# MainBoard.net
KiCad netlist of a schematic drawn in EAGLE
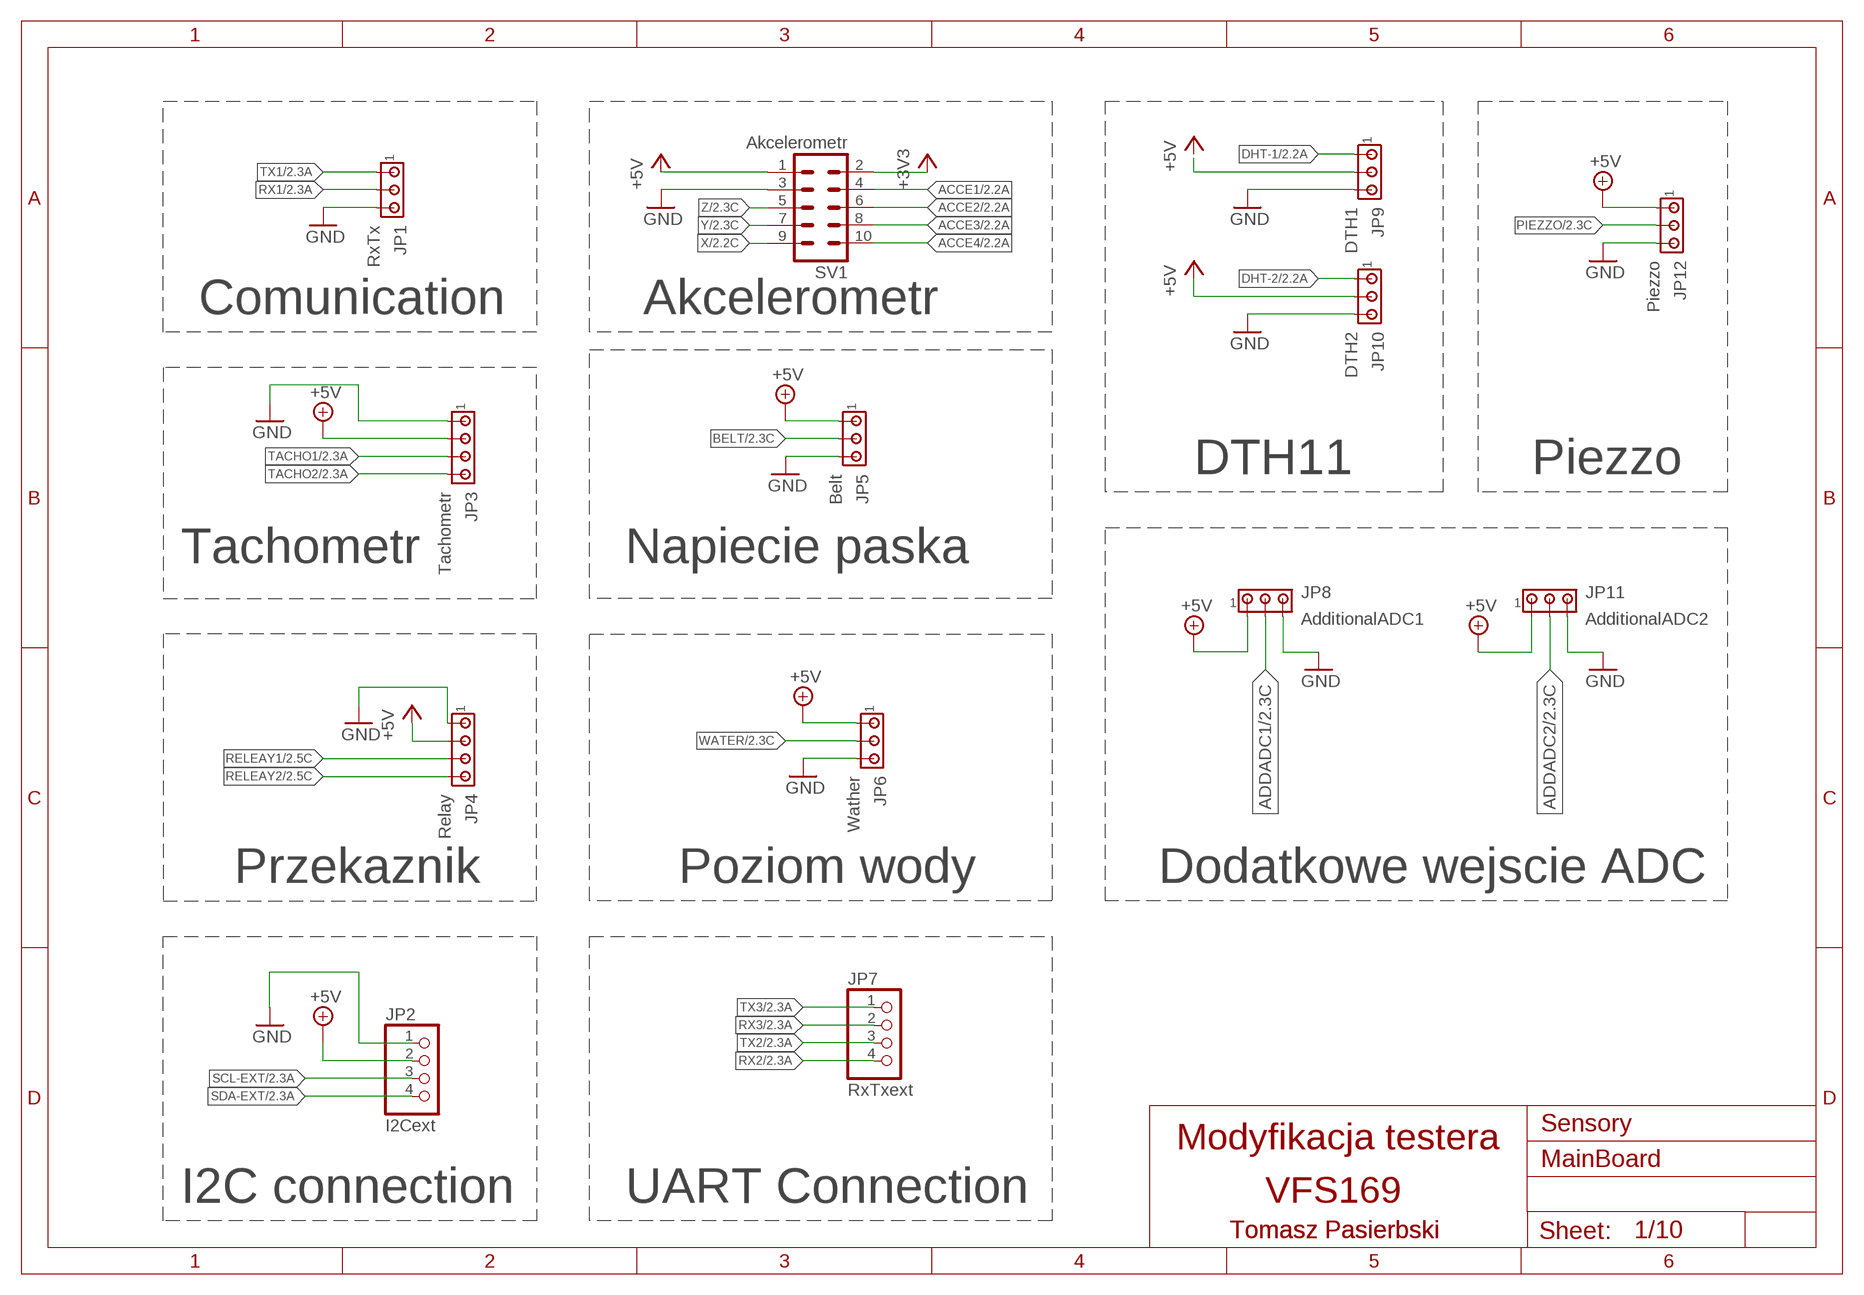
[diagram p0: schematic, sheet 1]
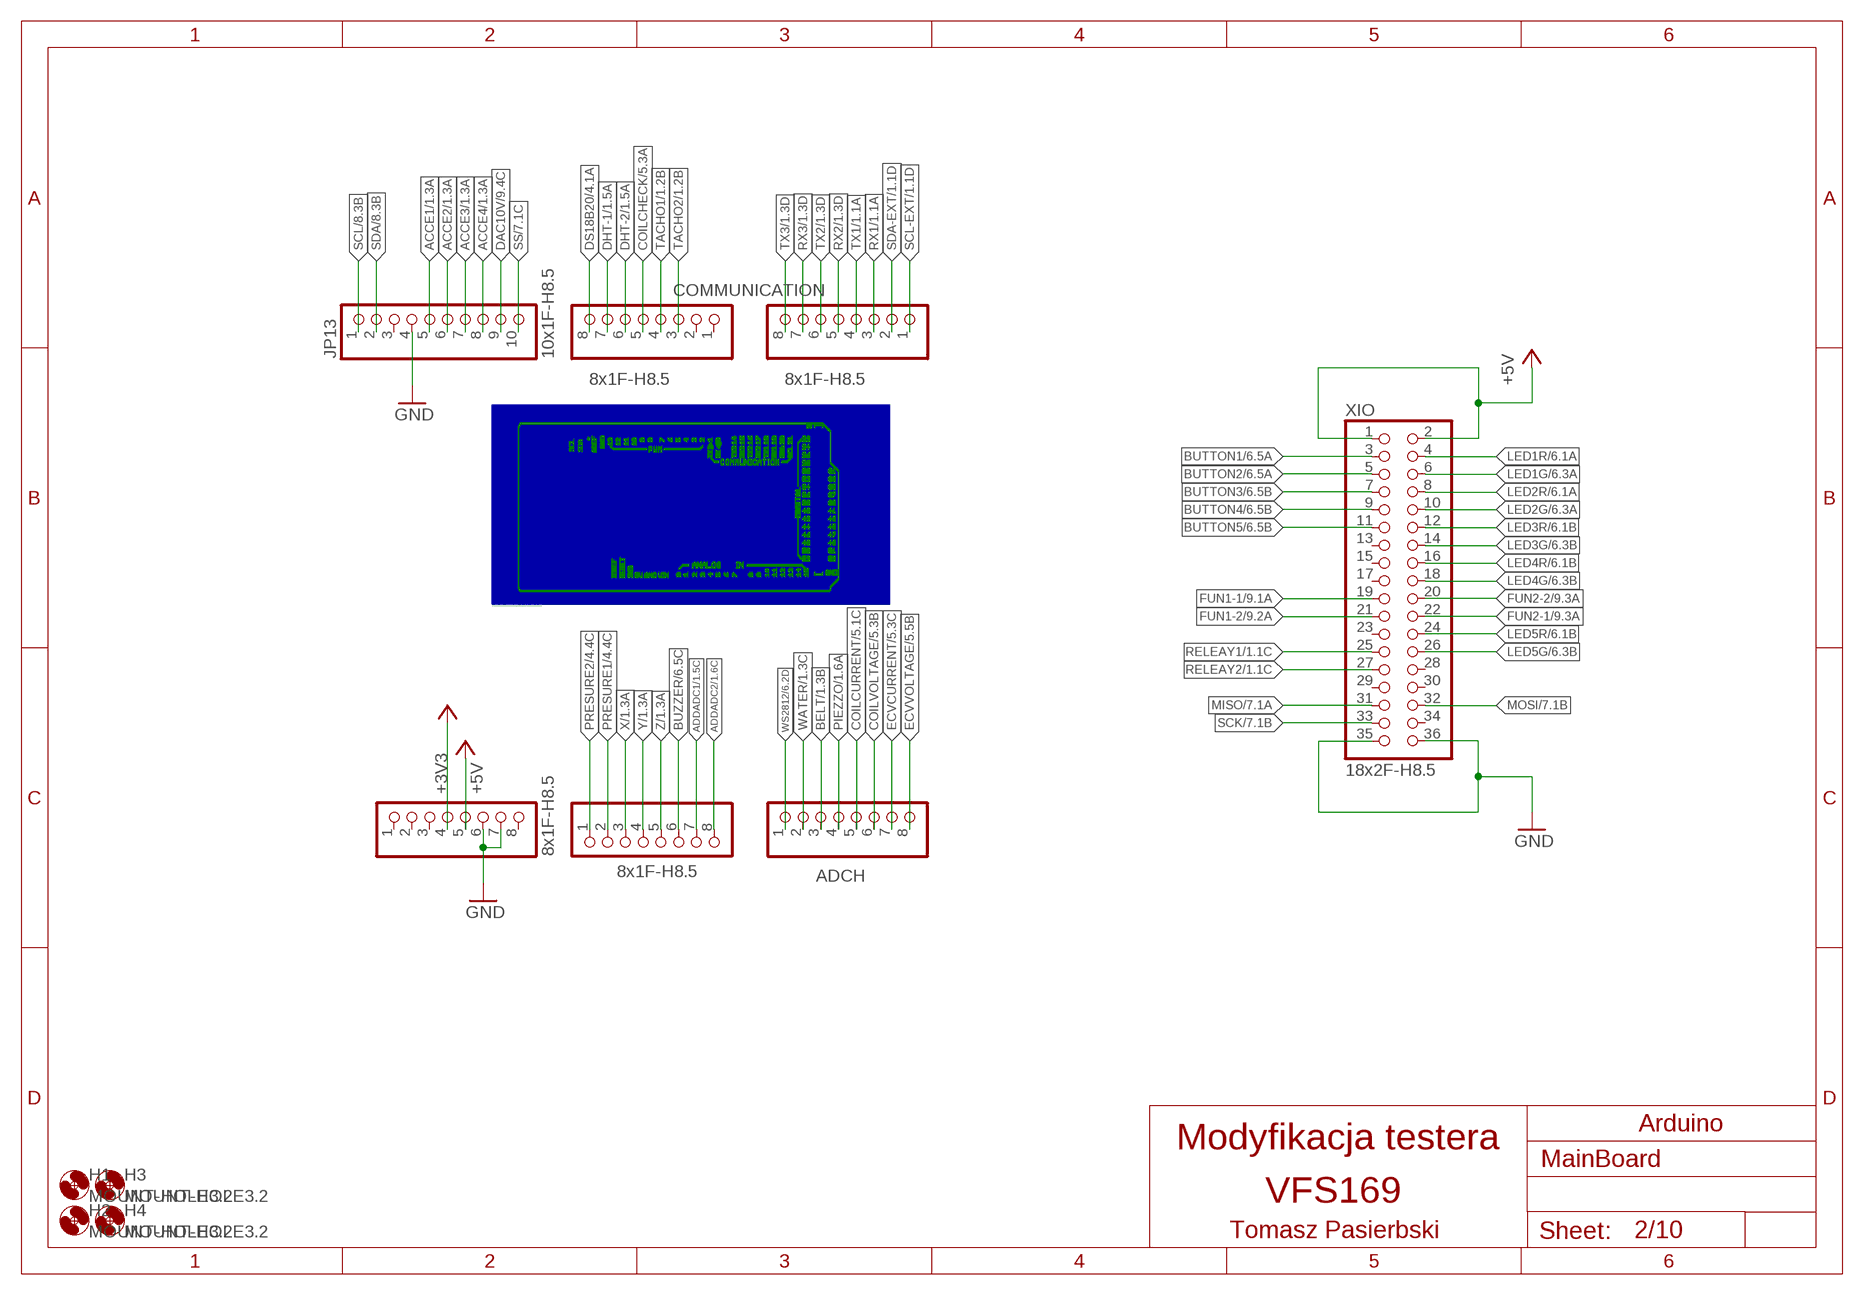
[diagram p1: schematic, sheet 2]
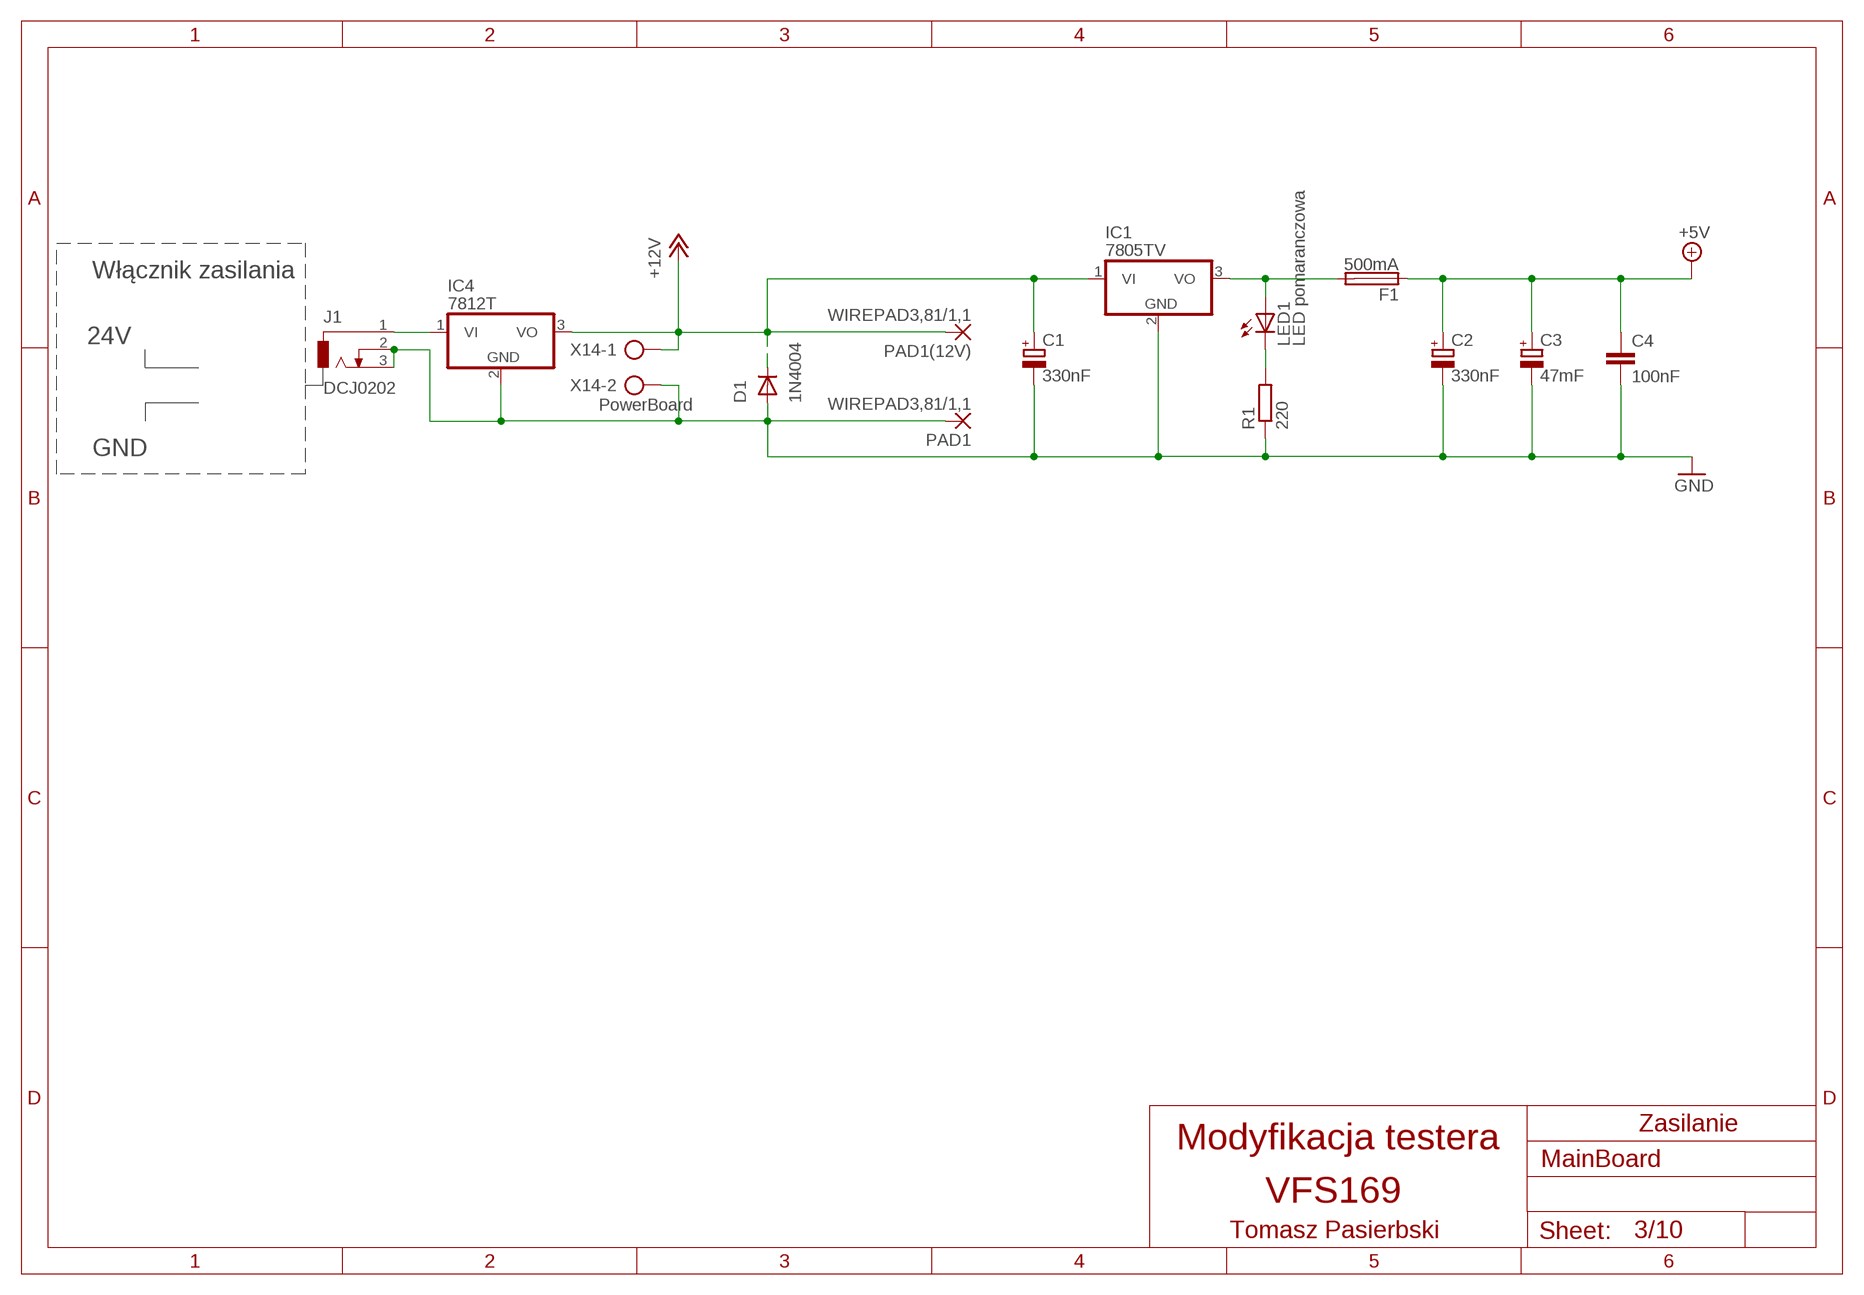
[diagram p2: schematic, sheet 3]
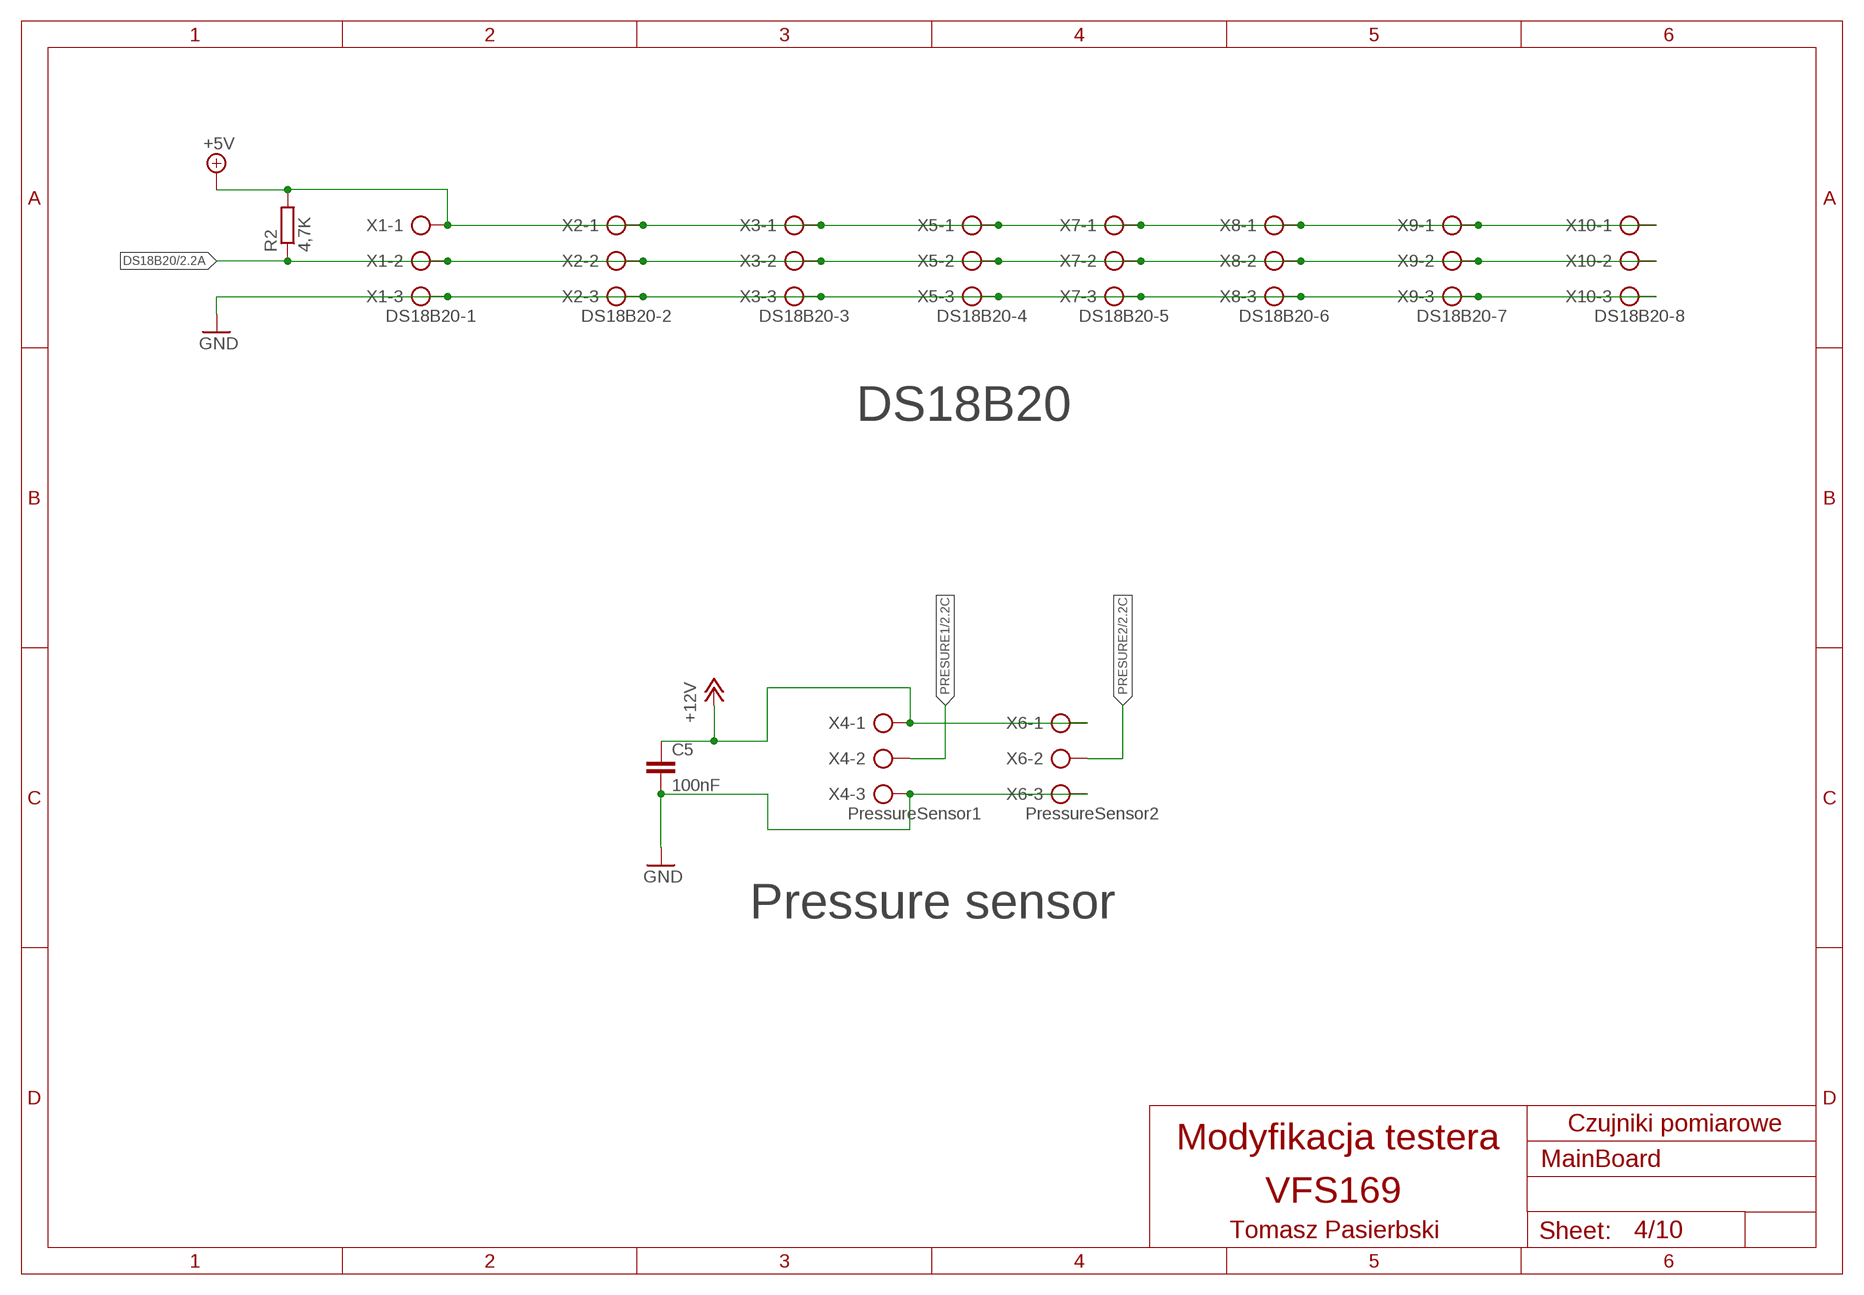
[diagram p3: schematic, sheet 4]
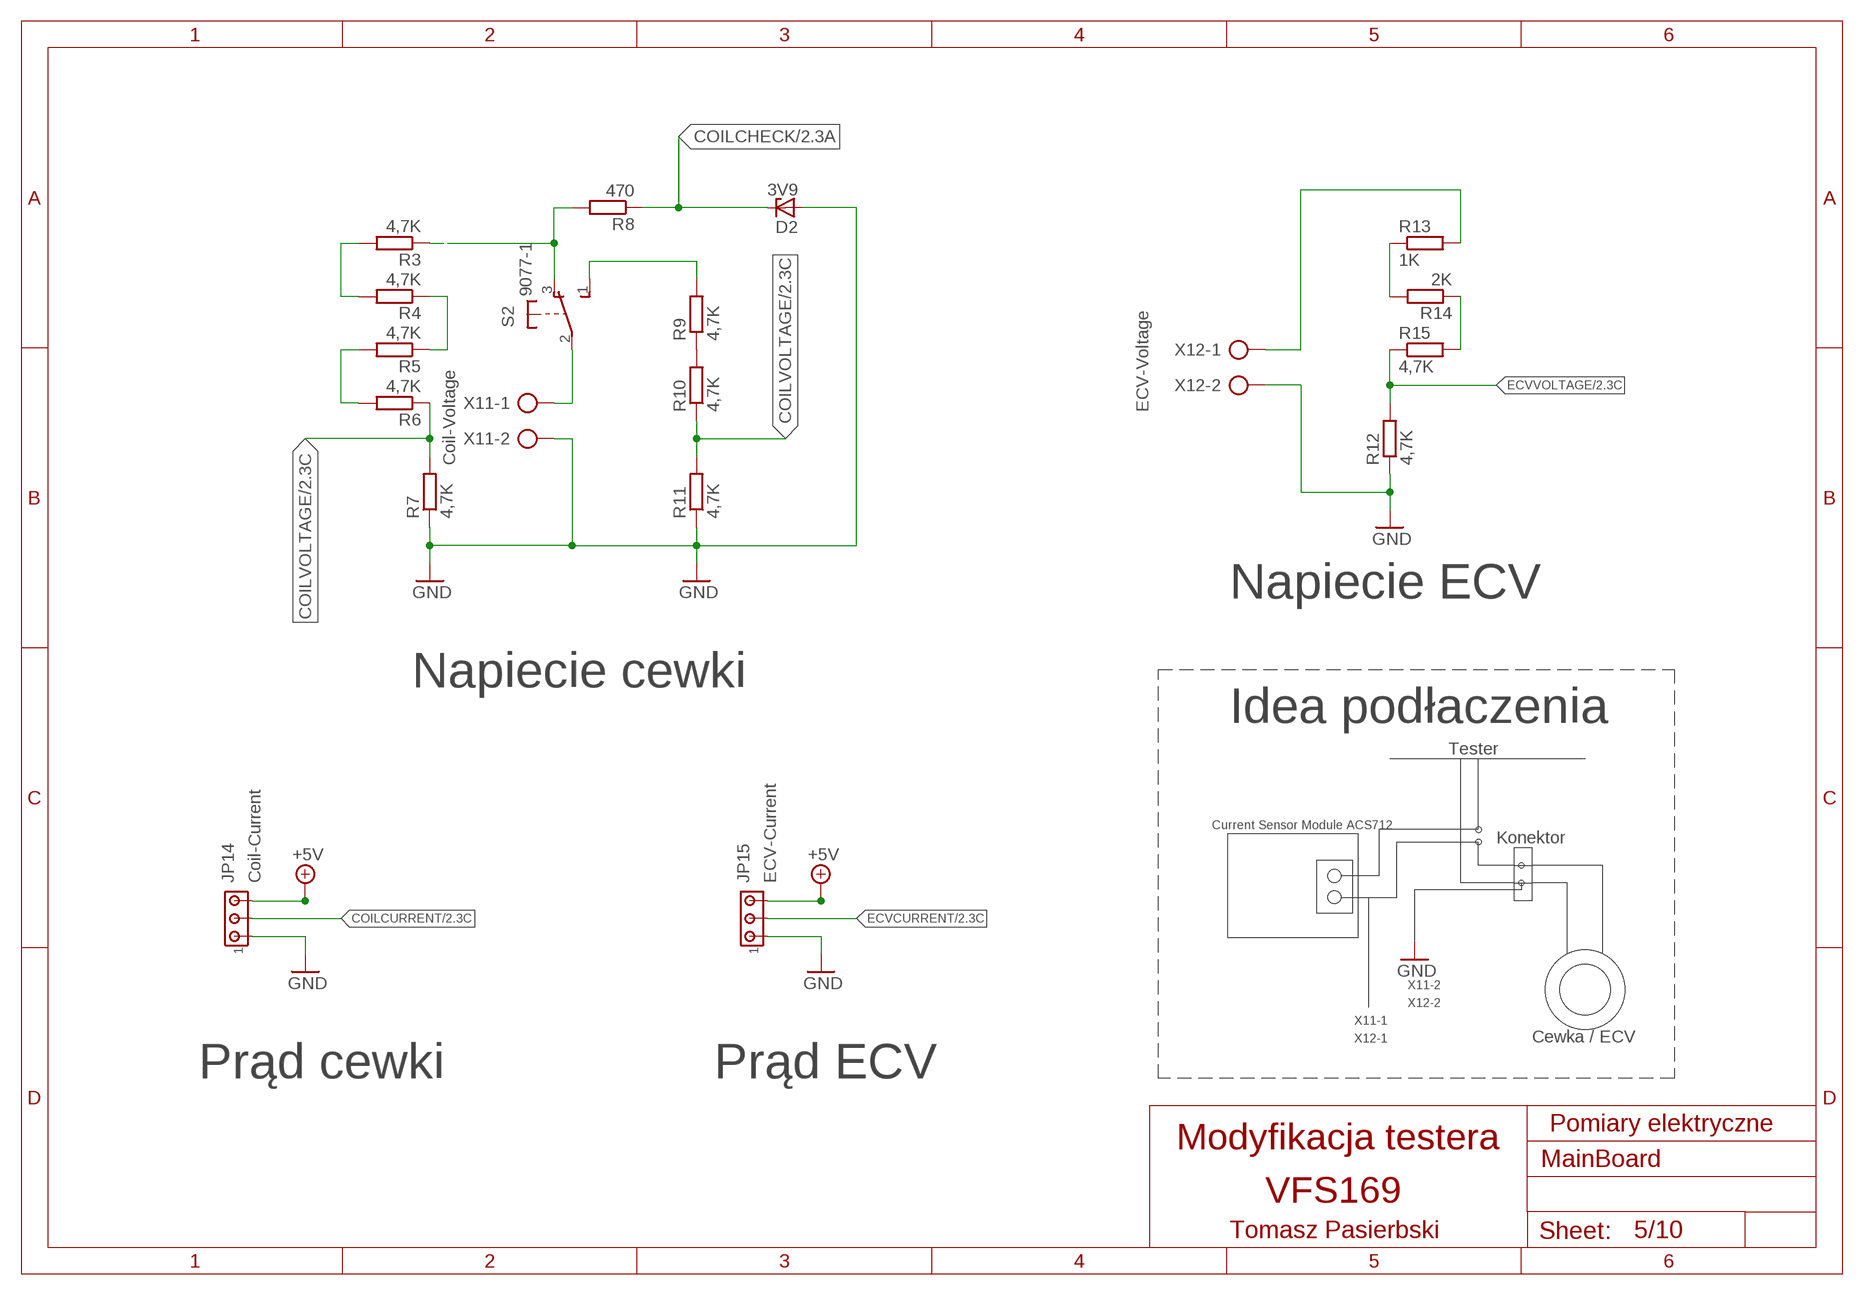
[diagram p4: schematic, sheet 5]
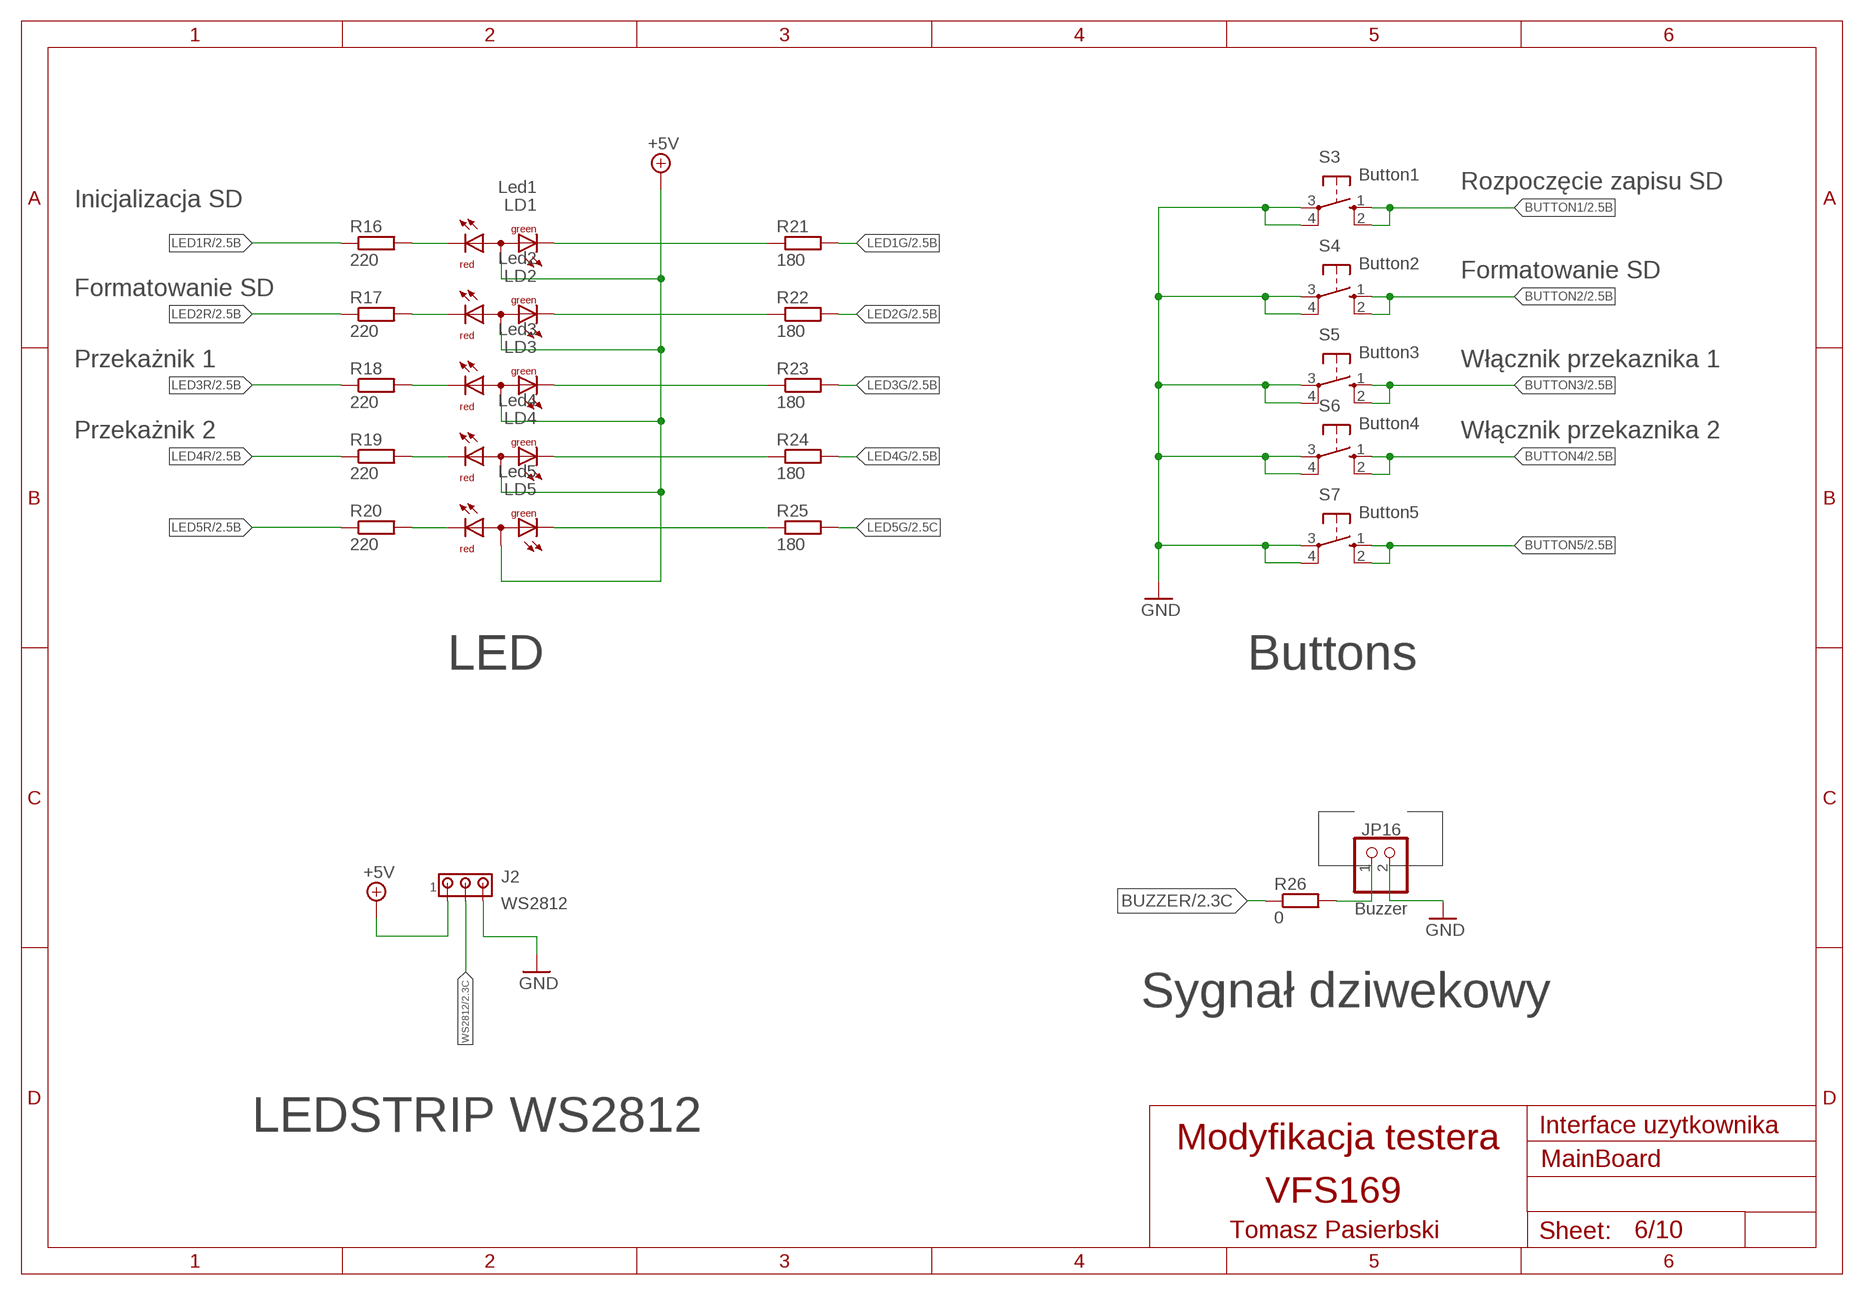
[diagram p5: schematic, sheet 6]
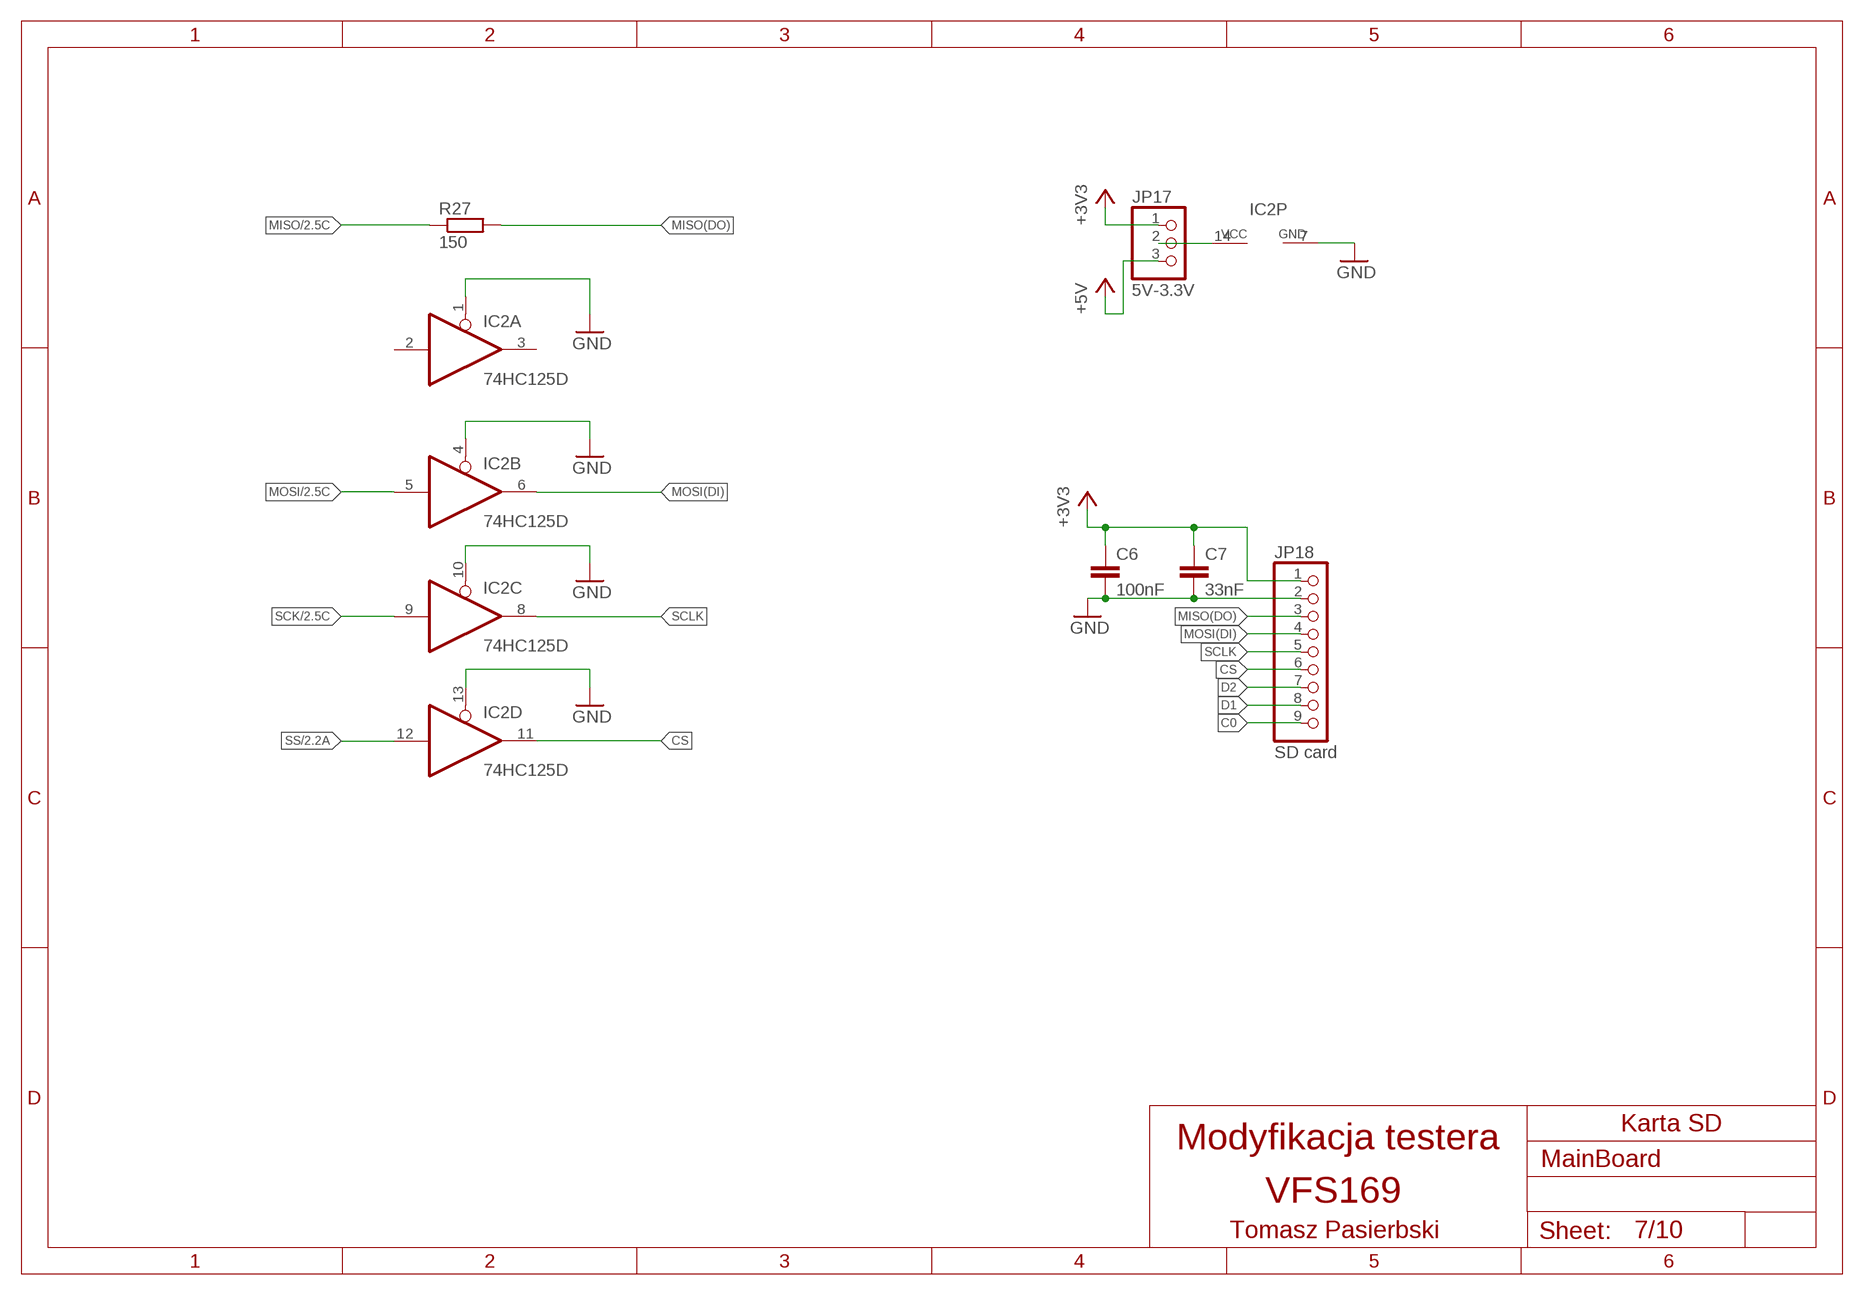
[diagram p6: schematic, sheet 7]
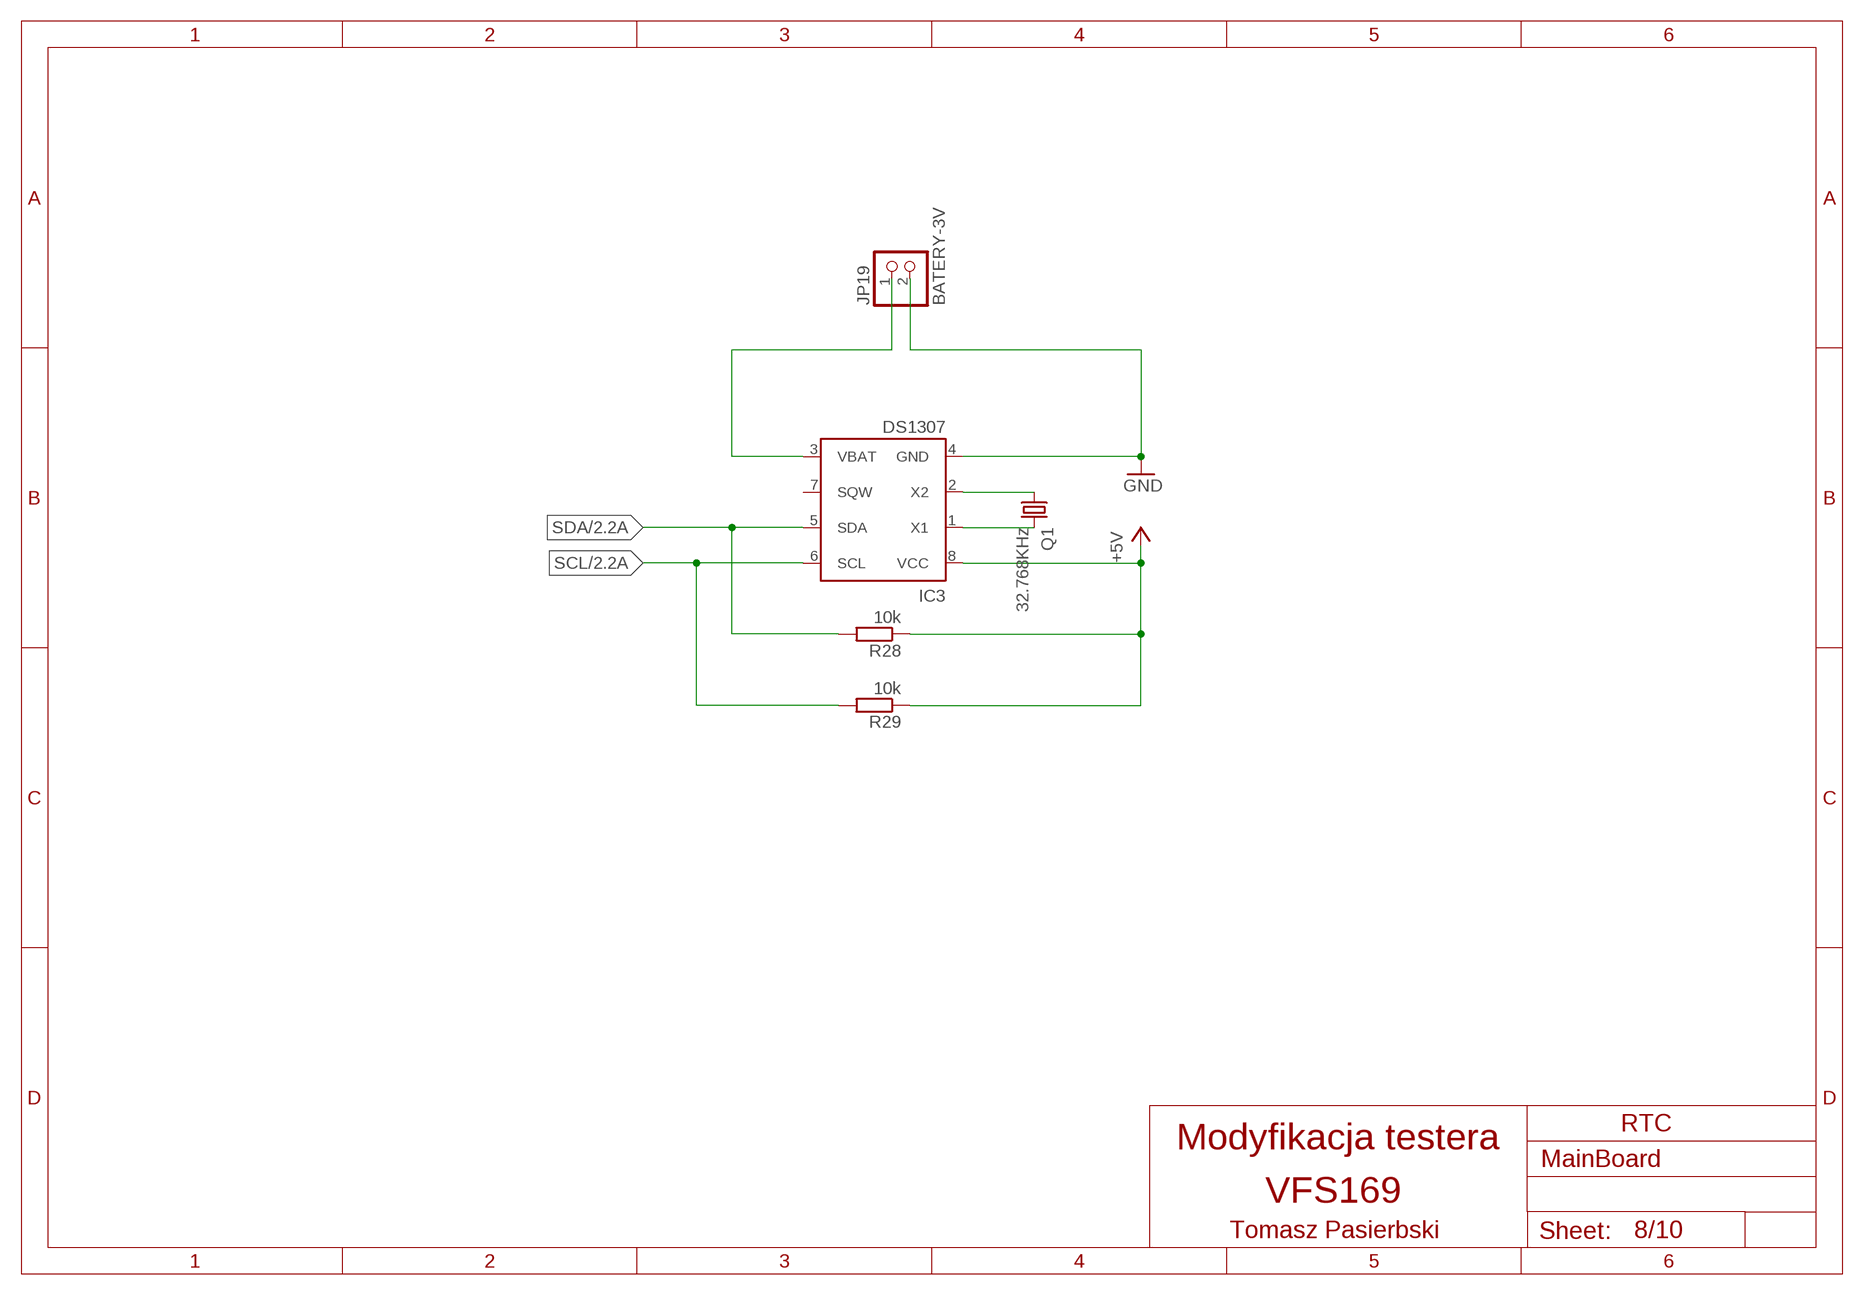
[diagram p7: schematic, sheet 8]
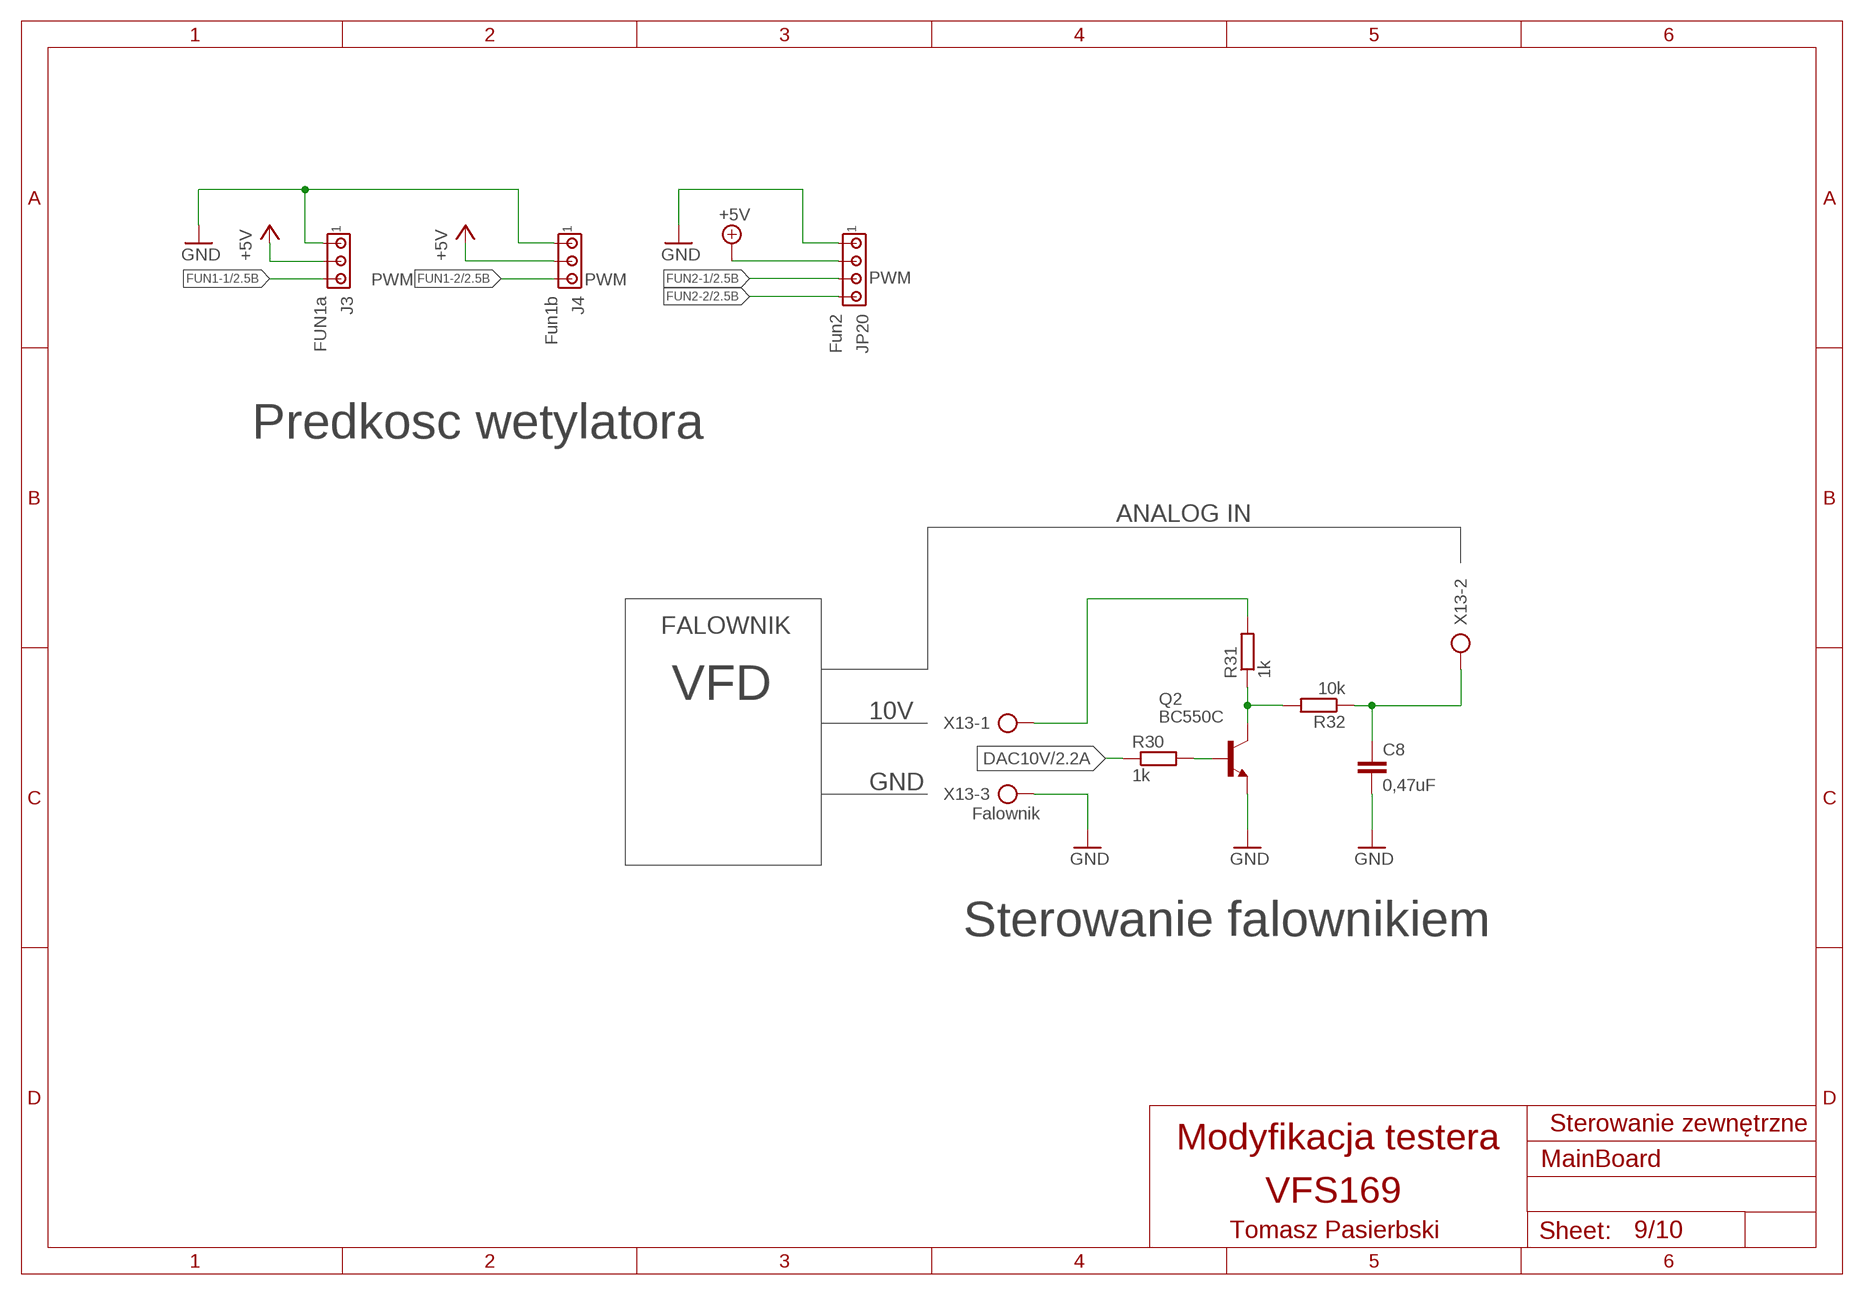
[diagram p8: schematic, sheet 9]
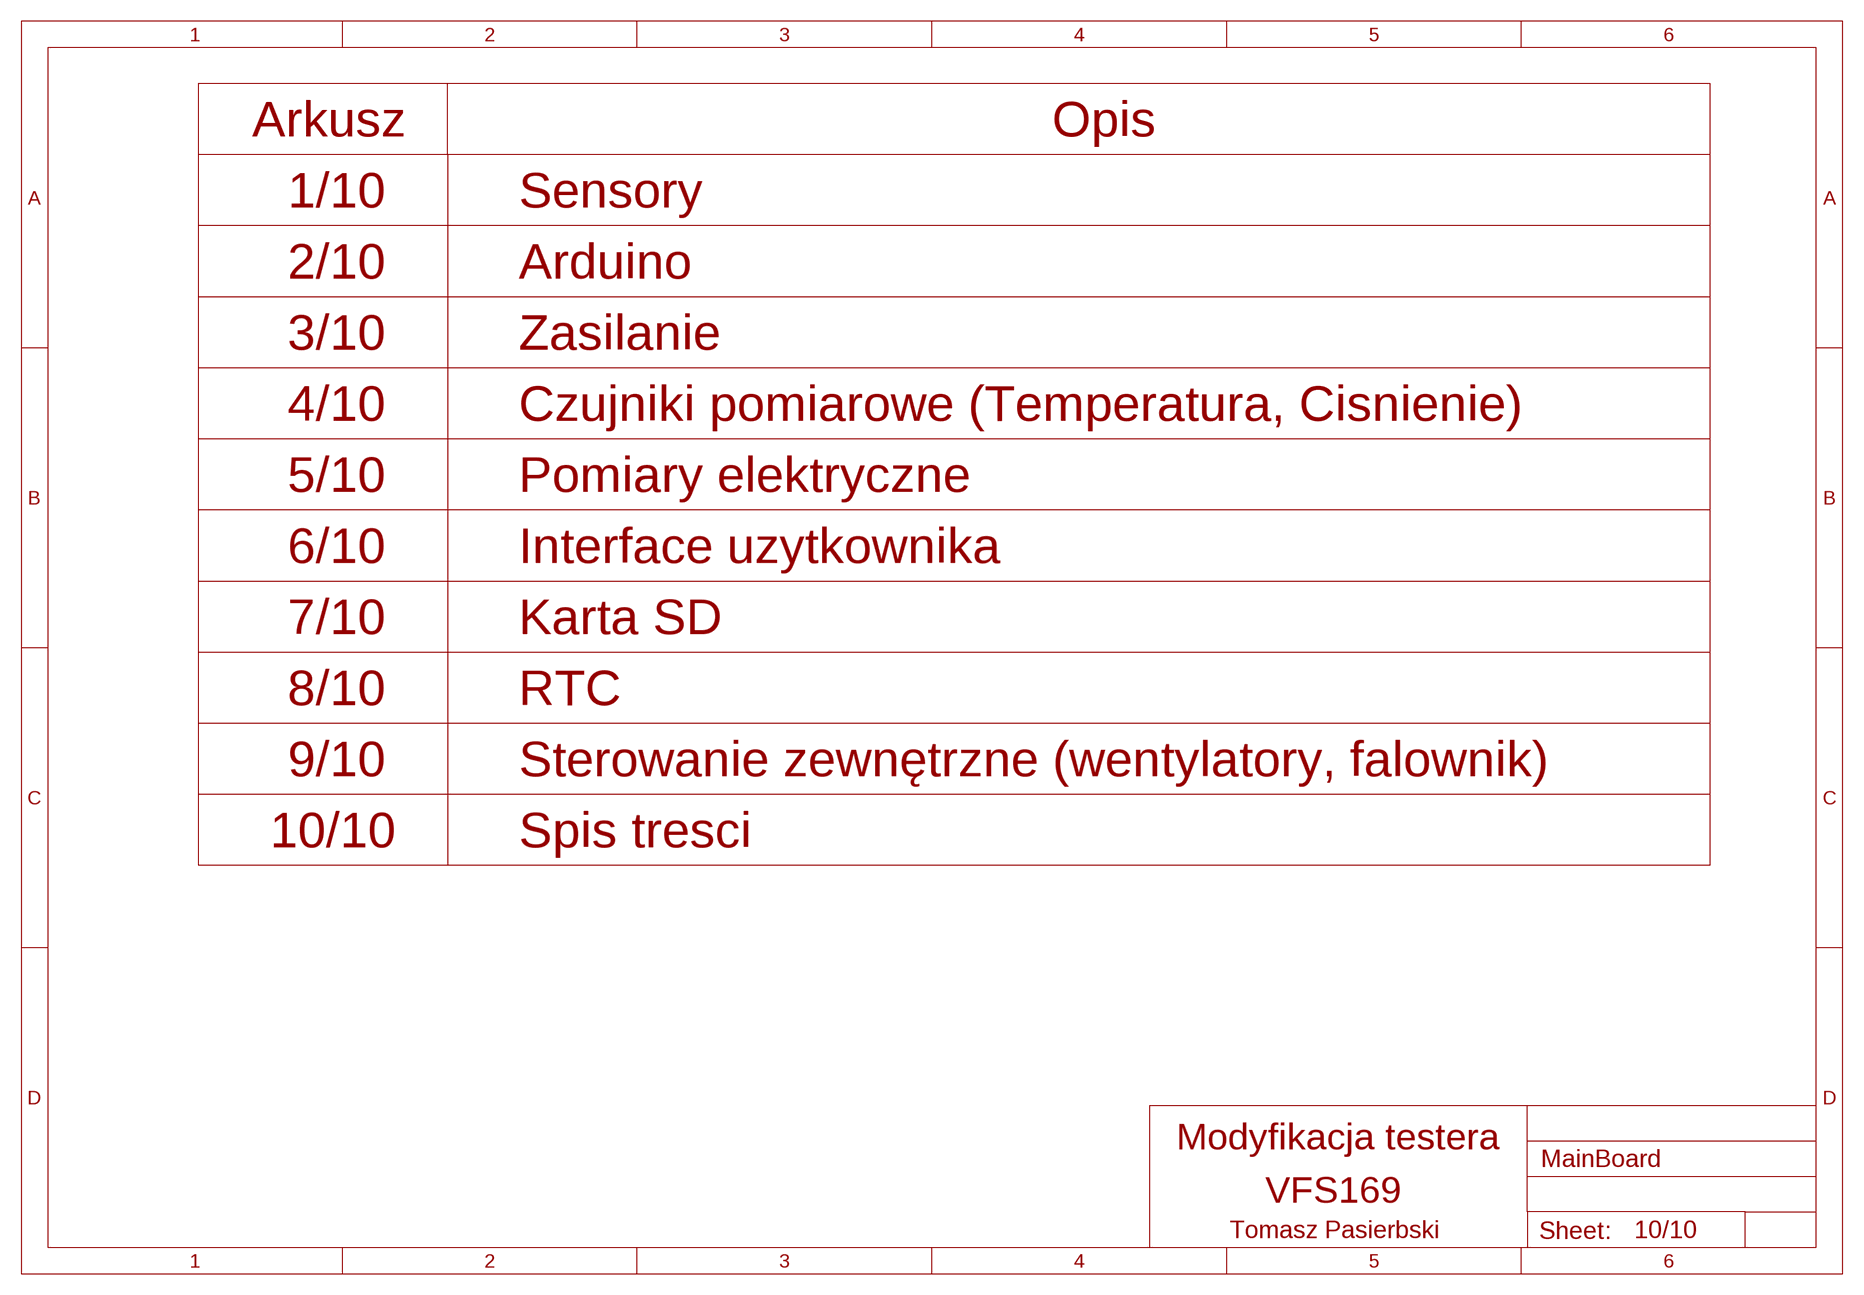
[diagram p9: schematic, sheet 10]

(export (version "E")
  (design (tool "Eeschema 10.0.6"))
  (components
    (comp (ref "ADCH")
      (value "8x1F-H8.5")
      (footprint "eagle-import:1X08")
      (libsource (lib "eagle-import") (part "pinhead_PINHD-1X8"))
    )
    (comp (ref "ADCL")
      (value "8x1F-H8.5")
      (footprint "eagle-import:1X08")
      (libsource (lib "eagle-import") (part "pinhead_PINHD-1X8"))
    )
    (comp (ref "COMMUNICATION")
      (value "8x1F-H8.5")
      (footprint "eagle-import:1X08")
      (libsource (lib "eagle-import") (part "pinhead_PINHD-1X8"))
    )
    (comp (ref "H1")
      (value "MOUNT-HOLE3.2")
      (footprint "eagle-import:3,2")
      (libsource (lib "eagle-import") (part "MOUNT-HOLE3.2"))
    )
    (comp (ref "H2")
      (value "MOUNT-HOLE3.2")
      (footprint "eagle-import:3,2")
      (libsource (lib "eagle-import") (part "MOUNT-HOLE3.2"))
    )
    (comp (ref "H3")
      (value "MOUNT-HOLE3.2")
      (footprint "eagle-import:3,2")
      (libsource (lib "eagle-import") (part "MOUNT-HOLE3.2"))
    )
    (comp (ref "H4")
      (value "MOUNT-HOLE3.2")
      (footprint "eagle-import:3,2")
      (libsource (lib "eagle-import") (part "MOUNT-HOLE3.2"))
    )
    (comp (ref "JP13")
      (value "10x1F-H8.5")
      (footprint "eagle-import:1X10")
      (libsource (lib "eagle-import") (part "PINHD-1X10"))
    )
    (comp (ref "POWER")
      (value "8x1F-H8.5")
      (footprint "eagle-import:1X08@1")
      (libsource (lib "eagle-import") (part "PINHD-1X8"))
    )
    (comp (ref "PWML")
      (value "8x1F-H8.5")
      (footprint "eagle-import:1X08")
      (libsource (lib "eagle-import") (part "pinhead_PINHD-1X8"))
    )
    (comp (ref "XIO")
      (value "18x2F-H8.5")
      (footprint "eagle-import:2X18")
      (libsource (lib "eagle-import") (part "PINHD-2X18"))
    )
    (comp (ref "D2")
      (value "3V9")
      (footprint "eagle-import:ZDIO-7.5")
      (libsource (lib "eagle-import") (part "ZENER-DIODEZD-7.5"))
    )
    (comp (ref "JP14")
      (value "Coil-Current")
      (footprint "eagle-import:10X03MTA")
      (libsource (lib "eagle-import") (part "MTA03-100"))
    )
    (comp (ref "JP15")
      (value "ECV-Current")
      (footprint "eagle-import:10X03MTA")
      (libsource (lib "eagle-import") (part "MTA03-100"))
    )
    (comp (ref "R3")
      (value "4,7K")
      (footprint "eagle-import:0207_10")
      (libsource (lib "eagle-import") (part "R-EU_0207/10"))
    )
    (comp (ref "R4")
      (value "4,7K")
      (footprint "eagle-import:0207_10")
      (libsource (lib "eagle-import") (part "R-EU_0207/10"))
    )
    (comp (ref "R5")
      (value "4,7K")
      (footprint "eagle-import:0207_10")
      (libsource (lib "eagle-import") (part "R-EU_0207/10"))
    )
    (comp (ref "R6")
      (value "4,7K")
      (footprint "eagle-import:0207_10")
      (libsource (lib "eagle-import") (part "R-EU_0207/10"))
    )
    (comp (ref "R7")
      (value "4,7K")
      (footprint "eagle-import:0207_10")
      (libsource (lib "eagle-import") (part "R-EU_0207/10"))
    )
    (comp (ref "R8")
      (value "470")
      (footprint "eagle-import:0207_10")
      (libsource (lib "eagle-import") (part "R-EU_0207/10"))
    )
    (comp (ref "R9")
      (value "4,7K")
      (footprint "eagle-import:0207_10")
      (libsource (lib "eagle-import") (part "R-EU_0207/10"))
    )
    (comp (ref "R10")
      (value "4,7K")
      (footprint "eagle-import:0207_10")
      (libsource (lib "eagle-import") (part "R-EU_0207/10"))
    )
    (comp (ref "R11")
      (value "4,7K")
      (footprint "eagle-import:0207_10")
      (libsource (lib "eagle-import") (part "R-EU_0207/10"))
    )
    (comp (ref "R12")
      (value "4,7K")
      (footprint "eagle-import:0207_10")
      (libsource (lib "eagle-import") (part "R-EU_0207/10"))
    )
    (comp (ref "R13")
      (value "1K")
      (footprint "eagle-import:0207_10")
      (libsource (lib "eagle-import") (part "R-EU_0207/10"))
    )
    (comp (ref "R14")
      (value "2K")
      (footprint "eagle-import:0207_10")
      (libsource (lib "eagle-import") (part "R-EU_0207/10"))
    )
    (comp (ref "R15")
      (value "4,7K")
      (footprint "eagle-import:0207_10")
      (libsource (lib "eagle-import") (part "R-EU_0207/10"))
    )
    (comp (ref "S2")
      (value "9077-1")
      (footprint "eagle-import:9077-1")
      (libsource (lib "eagle-import") (part "9077-1"))
    )
    (comp (ref "X11")
      (value "Coil-Voltage")
      (footprint "eagle-import:AK300_2")
      (libsource (lib "eagle-import") (part "AK300/2"))
    )
    (comp (ref "X12")
      (value "ECV-Voltage")
      (footprint "eagle-import:AK300_2")
      (libsource (lib "eagle-import") (part "AK300/2"))
    )
    (comp (ref "J2")
      (value "WS2812")
      (footprint "eagle-import:10X03MTA")
      (libsource (lib "eagle-import") (part "MTA03-100"))
    )
    (comp (ref "JP16")
      (value "Buzzer")
      (footprint "eagle-import:1X02")
      (libsource (lib "eagle-import") (part "PINHD-1X2"))
    )
    (comp (ref "LD1")
      (value "Led1")
      (footprint "eagle-import:DUOLED-A-5MM")
      (libsource (lib "eagle-import") (part "DUOLED-RG-A"))
    )
    (comp (ref "LD2")
      (value "Led2")
      (footprint "eagle-import:DUOLED-A-5MM")
      (libsource (lib "eagle-import") (part "DUOLED-RG-A"))
    )
    (comp (ref "LD3")
      (value "Led3")
      (footprint "eagle-import:DUOLED-A-5MM")
      (libsource (lib "eagle-import") (part "DUOLED-RG-A"))
    )
    (comp (ref "LD4")
      (value "Led4")
      (footprint "eagle-import:DUOLED-A-5MM")
      (libsource (lib "eagle-import") (part "DUOLED-RG-A"))
    )
    (comp (ref "LD5")
      (value "Led5")
      (footprint "eagle-import:DUOLED-A-5MM")
      (libsource (lib "eagle-import") (part "DUOLED-RG-A"))
    )
    (comp (ref "R16")
      (value "220")
      (footprint "eagle-import:0204_7")
      (libsource (lib "eagle-import") (part "R-EU_0204/7"))
    )
    (comp (ref "R17")
      (value "220")
      (footprint "eagle-import:0204_7")
      (libsource (lib "eagle-import") (part "R-EU_0204/7"))
    )
    (comp (ref "R18")
      (value "220")
      (footprint "eagle-import:0204_7")
      (libsource (lib "eagle-import") (part "R-EU_0204/7"))
    )
    (comp (ref "R19")
      (value "220")
      (footprint "eagle-import:0204_7")
      (libsource (lib "eagle-import") (part "R-EU_0204/7"))
    )
    (comp (ref "R20")
      (value "220")
      (footprint "eagle-import:0204_7")
      (libsource (lib "eagle-import") (part "R-EU_0204/7"))
    )
    (comp (ref "R21")
      (value "180")
      (footprint "eagle-import:0204_7")
      (libsource (lib "eagle-import") (part "R-EU_0204/7"))
    )
    (comp (ref "R22")
      (value "180")
      (footprint "eagle-import:0204_7")
      (libsource (lib "eagle-import") (part "R-EU_0204/7"))
    )
    (comp (ref "R23")
      (value "180")
      (footprint "eagle-import:0204_7")
      (libsource (lib "eagle-import") (part "R-EU_0204/7"))
    )
    (comp (ref "R24")
      (value "180")
      (footprint "eagle-import:0204_7")
      (libsource (lib "eagle-import") (part "R-EU_0204/7"))
    )
    (comp (ref "R25")
      (value "180")
      (footprint "eagle-import:0204_7")
      (libsource (lib "eagle-import") (part "R-EU_0204/7"))
    )
    (comp (ref "R26")
      (value "0")
      (footprint "eagle-import:0207_10")
      (libsource (lib "eagle-import") (part "R-EU_0207/10"))
    )
    (comp (ref "S3")
      (value "Button1")
      (footprint "eagle-import:B3F-10XX")
      (fields (field (name "MPN") "B3F-1000"))
      (libsource (lib "eagle-import") (part "10-XX"))
    )
    (comp (ref "S4")
      (value "Button2")
      (footprint "eagle-import:B3F-10XX")
      (fields (field (name "MPN") "B3F-1000"))
      (libsource (lib "eagle-import") (part "10-XX"))
    )
    (comp (ref "S5")
      (value "Button3")
      (footprint "eagle-import:B3F-10XX")
      (fields (field (name "MPN") "B3F-1000"))
      (libsource (lib "eagle-import") (part "10-XX"))
    )
    (comp (ref "S6")
      (value "Button4")
      (footprint "eagle-import:B3F-10XX")
      (fields (field (name "MPN") "B3F-1000"))
      (libsource (lib "eagle-import") (part "10-XX"))
    )
    (comp (ref "S7")
      (value "Button5")
      (footprint "eagle-import:B3F-10XX")
      (fields (field (name "MPN") "B3F-1000"))
      (libsource (lib "eagle-import") (part "10-XX"))
    )
    (comp (ref "C8")
      (value "0,47uF")
      (footprint "eagle-import:C025-025X050")
      (libsource (lib "eagle-import") (part "C-EU025-025X050"))
    )
    (comp (ref "J3")
      (value "FUN1a")
      (footprint "eagle-import:10X03MTA")
      (libsource (lib "eagle-import") (part "MTA03-100"))
    )
    (comp (ref "J4")
      (value "Fun1b")
      (footprint "eagle-import:10X03MTA")
      (libsource (lib "eagle-import") (part "MTA03-100"))
    )
    (comp (ref "JP20")
      (value "Fun2")
      (footprint "eagle-import:10X04MTA")
      (libsource (lib "eagle-import") (part "MTA04-100"))
    )
    (comp (ref "Q2")
      (value "BC550C")
      (footprint "eagle-import:TO92-EBC")
      (libsource (lib "eagle-import") (part "BC550C"))
    )
    (comp (ref "R30")
      (value "1k")
      (footprint "eagle-import:0207_10")
      (libsource (lib "eagle-import") (part "R-EU_0207/10"))
    )
    (comp (ref "R31")
      (value "1k")
      (footprint "eagle-import:0207_10")
      (libsource (lib "eagle-import") (part "R-EU_0207/10"))
    )
    (comp (ref "R32")
      (value "10k")
      (footprint "eagle-import:0207_10")
      (libsource (lib "eagle-import") (part "R-EU_0207/10"))
    )
    (comp (ref "X13")
      (value "Falownik")
      (footprint "eagle-import:AK300_3")
      (libsource (lib "eagle-import") (part "AK300/3"))
    )
    (comp (ref "JP1")
      (value "RxTx")
      (footprint "eagle-import:10X03MTA")
      (libsource (lib "eagle-import") (part "MTA03-100"))
    )
    (comp (ref "JP2")
      (value "I2Cext")
      (footprint "eagle-import:1X04")
      (libsource (lib "eagle-import") (part "PINHD-1X4"))
    )
    (comp (ref "JP3")
      (value "Tachometr")
      (footprint "eagle-import:10X04MTA")
      (libsource (lib "eagle-import") (part "MTA04-100"))
    )
    (comp (ref "JP4")
      (value "Relay")
      (footprint "eagle-import:10X04MTA")
      (libsource (lib "eagle-import") (part "MTA04-100"))
    )
    (comp (ref "JP5")
      (value "Belt")
      (footprint "eagle-import:10X03MTA")
      (libsource (lib "eagle-import") (part "MTA03-100"))
    )
    (comp (ref "JP6")
      (value "Wather")
      (footprint "eagle-import:10X03MTA")
      (libsource (lib "eagle-import") (part "MTA03-100"))
    )
    (comp (ref "JP7")
      (value "RxTxext")
      (footprint "eagle-import:1X04")
      (libsource (lib "eagle-import") (part "PINHD-1X4"))
    )
    (comp (ref "JP8")
      (value "AdditionalADC1")
      (footprint "eagle-import:10X03MTA")
      (libsource (lib "eagle-import") (part "MTA03-100"))
    )
    (comp (ref "JP9")
      (value "DTH1")
      (footprint "eagle-import:10X03MTA")
      (libsource (lib "eagle-import") (part "MTA03-100"))
    )
    (comp (ref "JP10")
      (value "DTH2")
      (footprint "eagle-import:10X03MTA")
      (libsource (lib "eagle-import") (part "MTA03-100"))
    )
    (comp (ref "JP11")
      (value "AdditionalADC2")
      (footprint "eagle-import:10X03MTA")
      (libsource (lib "eagle-import") (part "MTA03-100"))
    )
    (comp (ref "JP12")
      (value "Piezzo")
      (footprint "eagle-import:10X03MTA")
      (libsource (lib "eagle-import") (part "MTA03-100"))
    )
    (comp (ref "SV1")
      (value "Akcelerometr")
      (footprint "eagle-import:ML10")
      (libsource (lib "eagle-import") (part "ML10"))
    )
    (comp (ref "C6")
      (value "100nF")
      (footprint "eagle-import:C025-030X050")
      (libsource (lib "eagle-import") (part "C-EU025-030X050"))
    )
    (comp (ref "C7")
      (value "33nF")
      (footprint "eagle-import:C025-024X044")
      (libsource (lib "eagle-import") (part "C-EU025-024X044"))
    )
    (comp (ref "IC2")
      (value "74HC125D")
      (footprint "eagle-import:SO14")
      (libsource (lib "eagle-import") (part "74125DHC"))
    )
    (comp (ref "JP17")
      (value "5V-3.3V")
      (footprint "eagle-import:1X03")
      (libsource (lib "eagle-import") (part "PINHD-1X3"))
    )
    (comp (ref "JP18")
      (value "SD card")
      (footprint "eagle-import:1X09")
      (libsource (lib "eagle-import") (part "PINHD-1X9"))
    )
    (comp (ref "R27")
      (value "150")
      (footprint "eagle-import:0204_7")
      (libsource (lib "eagle-import") (part "R-EU_0204/7"))
    )
    (comp (ref "C1")
      (value "330nF")
      (footprint "eagle-import:E3,5-10")
      (libsource (lib "eagle-import") (part "CPOL-EUE3.5-10"))
    )
    (comp (ref "C2")
      (value "330nF")
      (footprint "eagle-import:E3,5-10")
      (libsource (lib "eagle-import") (part "CPOL-EUE3.5-10"))
    )
    (comp (ref "C3")
      (value "47mF")
      (footprint "eagle-import:E2,5-6")
      (libsource (lib "eagle-import") (part "CPOL-EUE2.5-6"))
    )
    (comp (ref "C4")
      (value "100nF")
      (footprint "eagle-import:C025-030X050")
      (libsource (lib "eagle-import") (part "C-EU025-030X050"))
    )
    (comp (ref "D1")
      (value "1N4004")
      (footprint "eagle-import:DO41-10")
      (libsource (lib "eagle-import") (part "1N4004"))
    )
    (comp (ref "F1")
      (value "500mA")
      (footprint "eagle-import:SH22,5A")
      (libsource (lib "eagle-import") (part "FUSESH22,5A"))
    )
    (comp (ref "IC1")
      (value "7805TV")
      (footprint "eagle-import:TO220V")
      (libsource (lib "eagle-import") (part "78TV05"))
    )
    (comp (ref "IC4")
      (value "7812T")
      (footprint "eagle-import:TO220H")
      (libsource (lib "eagle-import") (part "78T12"))
    )
    (comp (ref "J1")
      (value "DCJ0202")
      (footprint "eagle-import:DCJ0202")
      (libsource (lib "eagle-import") (part "DCJ0202"))
    )
    (comp (ref "LED1")
      (value "LED pomaranczowa")
      (footprint "eagle-import:LED5MM")
      (libsource (lib "eagle-import") (part "LED5MM"))
    )
    (comp (ref "PAD1")
      (value "WIREPAD3,81/1,1")
      (footprint "eagle-import:3,81_1,1")
      (libsource (lib "eagle-import") (part "WIREPAD3,81/1,1"))
    )
    (comp (ref "PAD1(12V)")
      (value "WIREPAD3,81/1,1")
      (footprint "eagle-import:3,81_1,1")
      (libsource (lib "eagle-import") (part "WIREPAD3,81/1,1"))
    )
    (comp (ref "R1")
      (value "220")
      (footprint "eagle-import:0204_7")
      (libsource (lib "eagle-import") (part "R-EU_0204/7"))
    )
    (comp (ref "X14")
      (value "PowerBoard")
      (footprint "eagle-import:AK300_2")
      (libsource (lib "eagle-import") (part "AK300/2"))
    )
    (comp (ref "IC3")
      (value "DS1307")
      (footprint "eagle-import:DIL08")
      (libsource (lib "eagle-import") (part "DS1307"))
    )
    (comp (ref "JP19")
      (value "BATERY-3V")
      (footprint "eagle-import:1X02")
      (libsource (lib "eagle-import") (part "PINHD-1X2"))
    )
    (comp (ref "Q1")
      (value "32.768KHz")
      (footprint "eagle-import:TC26H")
      (libsource (lib "eagle-import") (part "CRYSTALTC26H"))
    )
    (comp (ref "R28")
      (value "10k")
      (footprint "eagle-import:0207_10")
      (libsource (lib "eagle-import") (part "R-EU_0207/10"))
    )
    (comp (ref "R29")
      (value "10k")
      (footprint "eagle-import:0207_10")
      (libsource (lib "eagle-import") (part "R-EU_0207/10"))
    )
    (comp (ref "C5")
      (value "100nF")
      (footprint "eagle-import:C075-032X103")
      (libsource (lib "eagle-import") (part "C-EU075-032X103"))
    )
    (comp (ref "R2")
      (value "4,7K")
      (footprint "eagle-import:0207_12")
      (libsource (lib "eagle-import") (part "R-EU_0207/12"))
    )
    (comp (ref "X1")
      (value "DS18B20-1")
      (footprint "eagle-import:AK300_3")
      (libsource (lib "eagle-import") (part "AK300/3"))
    )
    (comp (ref "X2")
      (value "DS18B20-2")
      (footprint "eagle-import:AK300_3")
      (libsource (lib "eagle-import") (part "AK300/3"))
    )
    (comp (ref "X3")
      (value "DS18B20-3")
      (footprint "eagle-import:AK300_3")
      (libsource (lib "eagle-import") (part "AK300/3"))
    )
    (comp (ref "X4")
      (value "PressureSensor1")
      (footprint "eagle-import:AK300_3")
      (libsource (lib "eagle-import") (part "AK300/3"))
    )
    (comp (ref "X5")
      (value "DS18B20-4")
      (footprint "eagle-import:AK300_3")
      (libsource (lib "eagle-import") (part "AK300/3"))
    )
    (comp (ref "X6")
      (value "PressureSensor2")
      (footprint "eagle-import:AK300_3")
      (libsource (lib "eagle-import") (part "AK300/3"))
    )
    (comp (ref "X7")
      (value "DS18B20-5")
      (footprint "eagle-import:AK300_3")
      (libsource (lib "eagle-import") (part "AK300/3"))
    )
    (comp (ref "X8")
      (value "DS18B20-6")
      (footprint "eagle-import:AK300_3")
      (libsource (lib "eagle-import") (part "AK300/3"))
    )
    (comp (ref "X9")
      (value "DS18B20-7")
      (footprint "eagle-import:AK300_3")
      (libsource (lib "eagle-import") (part "AK300/3"))
    )
    (comp (ref "X10")
      (value "DS18B20-8")
      (footprint "eagle-import:AK300_3")
      (libsource (lib "eagle-import") (part "AK300/3"))
    )
  )
  (nets
    (net (code "1") (name "+3V3") (class "Default")
      (node (ref "C6") (pin "1") (pinfunction "1_1") (pintype "passive"))
      (node (ref "C7") (pin "1") (pinfunction "1_1") (pintype "passive"))
      (node (ref "JP17") (pin "1") (pinfunction "1_1") (pintype "passive"))
      (node (ref "JP18") (pin "1") (pinfunction "1_1") (pintype "passive"))
      (node (ref "POWER") (pin "4") (pinfunction "4_4") (pintype "passive"))
      (node (ref "SV1") (pin "2") (pinfunction "2_2") (pintype "passive"))
    )
    (net (code "2") (name "+5V") (class "Default")
      (node (ref "C2") (pin "+") (pinfunction "+_+") (pintype "passive"))
      (node (ref "C3") (pin "+") (pinfunction "+_+") (pintype "passive"))
      (node (ref "C4") (pin "1") (pinfunction "1_1") (pintype "passive"))
      (node (ref "F1") (pin "1") (pinfunction "1_1") (pintype "passive"))
      (node (ref "IC3") (pin "8") (pinfunction "VCC_8") (pintype "power_in"))
      (node (ref "J2") (pin "1") (pinfunction "1_1") (pintype "passive"))
      (node (ref "J3") (pin "2") (pinfunction "2_2") (pintype "passive"))
      (node (ref "J4") (pin "2") (pinfunction "2_2") (pintype "passive"))
      (node (ref "JP10") (pin "2") (pinfunction "2_2") (pintype "passive"))
      (node (ref "JP11") (pin "1") (pinfunction "1_1") (pintype "passive"))
      (node (ref "JP12") (pin "1") (pinfunction "1_1") (pintype "passive"))
      (node (ref "JP14") (pin "3") (pinfunction "3_3") (pintype "passive"))
      (node (ref "JP15") (pin "3") (pinfunction "3_3") (pintype "passive"))
      (node (ref "JP17") (pin "3") (pinfunction "3_3") (pintype "passive"))
      (node (ref "JP2") (pin "2") (pinfunction "2_2") (pintype "passive"))
      (node (ref "JP20") (pin "2") (pinfunction "2_2") (pintype "passive"))
      (node (ref "JP3") (pin "2") (pinfunction "2_2") (pintype "passive"))
      (node (ref "JP4") (pin "2") (pinfunction "2_2") (pintype "passive"))
      (node (ref "JP5") (pin "1") (pinfunction "1_1") (pintype "passive"))
      (node (ref "JP6") (pin "1") (pinfunction "1_1") (pintype "passive"))
      (node (ref "JP8") (pin "1") (pinfunction "1_1") (pintype "passive"))
      (node (ref "JP9") (pin "2") (pinfunction "2_2") (pintype "passive"))
      (node (ref "LD1") (pin "A") (pinfunction "A_A") (pintype "passive"))
      (node (ref "LD2") (pin "A") (pinfunction "A_A") (pintype "passive"))
      (node (ref "LD3") (pin "A") (pinfunction "A_A") (pintype "passive"))
      (node (ref "LD4") (pin "A") (pinfunction "A_A") (pintype "passive"))
      (node (ref "LD5") (pin "A") (pinfunction "A_A") (pintype "passive"))
      (node (ref "POWER") (pin "5") (pinfunction "5_5") (pintype "passive"))
      (node (ref "R2") (pin "2") (pinfunction "2_2") (pintype "passive"))
      (node (ref "R28") (pin "1") (pinfunction "1_1") (pintype "passive"))
      (node (ref "R29") (pin "1") (pinfunction "1_1") (pintype "passive"))
      (node (ref "SV1") (pin "1") (pinfunction "1_1") (pintype "passive"))
      (node (ref "X1") (pin "1") (pinfunction "KL_1") (pintype "passive"))
      (node (ref "X10") (pin "1") (pinfunction "KL_1") (pintype "passive"))
      (node (ref "X2") (pin "1") (pinfunction "KL_1") (pintype "passive"))
      (node (ref "X3") (pin "1") (pinfunction "KL_1") (pintype "passive"))
      (node (ref "X5") (pin "1") (pinfunction "KL_1") (pintype "passive"))
      (node (ref "X7") (pin "1") (pinfunction "KL_1") (pintype "passive"))
      (node (ref "X8") (pin "1") (pinfunction "KL_1") (pintype "passive"))
      (node (ref "X9") (pin "1") (pinfunction "KL_1") (pintype "passive"))
      (node (ref "XIO") (pin "1") (pinfunction "1_1") (pintype "passive"))
      (node (ref "XIO") (pin "2") (pinfunction "2_2") (pintype "passive"))
    )
    (net (code "3") (name "+12V") (class "Default")
      (node (ref "C1") (pin "+") (pinfunction "+_+") (pintype "passive"))
      (node (ref "C5") (pin "1") (pinfunction "1_1") (pintype "passive"))
      (node (ref "D1") (pin "C") (pinfunction "C_C") (pintype "passive"))
      (node (ref "IC1") (pin "1") (pinfunction "VI_1") (pintype "input"))
      (node (ref "IC4") (pin "3") (pinfunction "VO_3") (pintype "passive"))
      (node (ref "PAD1(12V)") (pin "1") (pinfunction "P_1") (pintype "passive"))
      (node (ref "X14") (pin "1") (pinfunction "KL_1") (pintype "passive"))
      (node (ref "X4") (pin "1") (pinfunction "KL_1") (pintype "passive"))
      (node (ref "X6") (pin "1") (pinfunction "KL_1") (pintype "passive"))
    )
    (net (code "4") (name "ACCE1") (class "Default")
      (node (ref "JP13") (pin "5") (pinfunction "5_5") (pintype "passive"))
      (node (ref "SV1") (pin "4") (pinfunction "4_4") (pintype "passive"))
    )
    (net (code "5") (name "ACCE2") (class "Default")
      (node (ref "JP13") (pin "6") (pinfunction "6_6") (pintype "passive"))
      (node (ref "SV1") (pin "6") (pinfunction "6_6") (pintype "passive"))
    )
    (net (code "6") (name "ACCE3") (class "Default")
      (node (ref "JP13") (pin "7") (pinfunction "7_7") (pintype "passive"))
      (node (ref "SV1") (pin "8") (pinfunction "8_8") (pintype "passive"))
    )
    (net (code "7") (name "ACCE4") (class "Default")
      (node (ref "JP13") (pin "8") (pinfunction "8_8") (pintype "passive"))
      (node (ref "SV1") (pin "10") (pinfunction "10_10") (pintype "passive"))
    )
    (net (code "8") (name "ADDADC1") (class "Default")
      (node (ref "ADCL") (pin "7") (pinfunction "7_7") (pintype "passive"))
      (node (ref "JP8") (pin "2") (pinfunction "2_2") (pintype "passive"))
    )
    (net (code "9") (name "ADDADC2") (class "Default")
      (node (ref "ADCL") (pin "8") (pinfunction "8_8") (pintype "passive"))
      (node (ref "JP11") (pin "2") (pinfunction "2_2") (pintype "passive"))
    )
    (net (code "10") (name "BELT") (class "Default")
      (node (ref "ADCH") (pin "3") (pinfunction "3_3") (pintype "passive"))
      (node (ref "JP5") (pin "2") (pinfunction "2_2") (pintype "passive"))
    )
    (net (code "11") (name "BUTTON1") (class "Default")
      (node (ref "S3") (pin "1") (pinfunction "S_1") (pintype "passive"))
      (node (ref "S3") (pin "2") (pinfunction "S1_2") (pintype "passive"))
      (node (ref "XIO") (pin "3") (pinfunction "3_3") (pintype "passive"))
    )
    (net (code "12") (name "BUTTON2") (class "Default")
      (node (ref "S4") (pin "1") (pinfunction "S_1") (pintype "passive"))
      (node (ref "S4") (pin "2") (pinfunction "S1_2") (pintype "passive"))
      (node (ref "XIO") (pin "5") (pinfunction "5_5") (pintype "passive"))
    )
    (net (code "13") (name "BUTTON3") (class "Default")
      (node (ref "S5") (pin "1") (pinfunction "S_1") (pintype "passive"))
      (node (ref "S5") (pin "2") (pinfunction "S1_2") (pintype "passive"))
      (node (ref "XIO") (pin "7") (pinfunction "7_7") (pintype "passive"))
    )
    (net (code "14") (name "BUTTON4") (class "Default")
      (node (ref "S6") (pin "1") (pinfunction "S_1") (pintype "passive"))
      (node (ref "S6") (pin "2") (pinfunction "S1_2") (pintype "passive"))
      (node (ref "XIO") (pin "9") (pinfunction "9_9") (pintype "passive"))
    )
    (net (code "15") (name "BUTTON5") (class "Default")
      (node (ref "S7") (pin "1") (pinfunction "S_1") (pintype "passive"))
      (node (ref "S7") (pin "2") (pinfunction "S1_2") (pintype "passive"))
      (node (ref "XIO") (pin "11") (pinfunction "11_11") (pintype "passive"))
    )
    (net (code "16") (name "BUZZER") (class "Default")
      (node (ref "ADCL") (pin "6") (pinfunction "6_6") (pintype "passive"))
      (node (ref "R26") (pin "1") (pinfunction "1_1") (pintype "passive"))
    )
    (net (code "17") (name "C0") (class "Default")
      (node (ref "JP18") (pin "9") (pinfunction "9_9") (pintype "passive"))
    )
    (net (code "18") (name "COILCHECK") (class "Default")
      (node (ref "D2") (pin "C") (pinfunction "C_C") (pintype "passive"))
      (node (ref "PWML") (pin "5") (pinfunction "5_5") (pintype "passive"))
      (node (ref "R8") (pin "1") (pinfunction "1_1") (pintype "passive"))
    )
    (net (code "19") (name "COILCURRENT") (class "Default")
      (node (ref "ADCH") (pin "5") (pinfunction "5_5") (pintype "passive"))
      (node (ref "JP14") (pin "2") (pinfunction "2_2") (pintype "passive"))
    )
    (net (code "20") (name "COILVOLTAGE") (class "Default")
      (node (ref "ADCH") (pin "6") (pinfunction "6_6") (pintype "passive"))
      (node (ref "R10") (pin "1") (pinfunction "1_1") (pintype "passive"))
      (node (ref "R11") (pin "2") (pinfunction "2_2") (pintype "passive"))
      (node (ref "R6") (pin "1") (pinfunction "1_1") (pintype "passive"))
      (node (ref "R7") (pin "2") (pinfunction "2_2") (pintype "passive"))
    )
    (net (code "21") (name "CS") (class "Default")
      (node (ref "IC2") (pin "11") (pinfunction "O_11") (pintype "tri_state"))
      (node (ref "JP18") (pin "6") (pinfunction "6_6") (pintype "passive"))
    )
    (net (code "22") (name "D1") (class "Default")
      (node (ref "JP18") (pin "8") (pinfunction "8_8") (pintype "passive"))
    )
    (net (code "23") (name "D2") (class "Default")
      (node (ref "JP18") (pin "7") (pinfunction "7_7") (pintype "passive"))
    )
    (net (code "24") (name "DAC10V") (class "Default")
      (node (ref "JP13") (pin "9") (pinfunction "9_9") (pintype "passive"))
      (node (ref "R30") (pin "1") (pinfunction "1_1") (pintype "passive"))
    )
    (net (code "25") (name "DHT-1") (class "Default")
      (node (ref "JP9") (pin "1") (pinfunction "1_1") (pintype "passive"))
      (node (ref "PWML") (pin "7") (pinfunction "7_7") (pintype "passive"))
    )
    (net (code "26") (name "DHT-2") (class "Default")
      (node (ref "JP10") (pin "1") (pinfunction "1_1") (pintype "passive"))
      (node (ref "PWML") (pin "6") (pinfunction "6_6") (pintype "passive"))
    )
    (net (code "27") (name "DS18B20") (class "Default")
      (node (ref "PWML") (pin "8") (pinfunction "8_8") (pintype "passive"))
      (node (ref "R2") (pin "1") (pinfunction "1_1") (pintype "passive"))
      (node (ref "X1") (pin "2") (pinfunction "KL_2") (pintype "passive"))
      (node (ref "X10") (pin "2") (pinfunction "KL_2") (pintype "passive"))
      (node (ref "X2") (pin "2") (pinfunction "KL_2") (pintype "passive"))
      (node (ref "X3") (pin "2") (pinfunction "KL_2") (pintype "passive"))
      (node (ref "X5") (pin "2") (pinfunction "KL_2") (pintype "passive"))
      (node (ref "X7") (pin "2") (pinfunction "KL_2") (pintype "passive"))
      (node (ref "X8") (pin "2") (pinfunction "KL_2") (pintype "passive"))
      (node (ref "X9") (pin "2") (pinfunction "KL_2") (pintype "passive"))
    )
    (net (code "28") (name "ECVCURRENT") (class "Default")
      (node (ref "ADCH") (pin "7") (pinfunction "7_7") (pintype "passive"))
      (node (ref "JP15") (pin "2") (pinfunction "2_2") (pintype "passive"))
    )
    (net (code "29") (name "ECVVOLTAGE") (class "Default")
      (node (ref "ADCH") (pin "8") (pinfunction "8_8") (pintype "passive"))
      (node (ref "R12") (pin "2") (pinfunction "2_2") (pintype "passive"))
      (node (ref "R15") (pin "1") (pinfunction "1_1") (pintype "passive"))
    )
    (net (code "30") (name "FUN1-1") (class "Default")
      (node (ref "J3") (pin "3") (pinfunction "3_3") (pintype "passive"))
      (node (ref "XIO") (pin "19") (pinfunction "19_19") (pintype "passive"))
    )
    (net (code "31") (name "FUN1-2") (class "Default")
      (node (ref "J4") (pin "3") (pinfunction "3_3") (pintype "passive"))
      (node (ref "XIO") (pin "21") (pinfunction "21_21") (pintype "passive"))
    )
    (net (code "32") (name "FUN2-1") (class "Default")
      (node (ref "JP20") (pin "3") (pinfunction "3_3") (pintype "passive"))
      (node (ref "XIO") (pin "22") (pinfunction "22_22") (pintype "passive"))
    )
    (net (code "33") (name "FUN2-2") (class "Default")
      (node (ref "JP20") (pin "4") (pinfunction "4_4") (pintype "passive"))
      (node (ref "XIO") (pin "20") (pinfunction "20_20") (pintype "passive"))
    )
    (net (code "34") (name "GND") (class "Default")
      (node (ref "C1") (pin "-") (pinfunction "-_-") (pintype "passive"))
      (node (ref "C2") (pin "-") (pinfunction "-_-") (pintype "passive"))
      (node (ref "C3") (pin "-") (pinfunction "-_-") (pintype "passive"))
      (node (ref "C4") (pin "2") (pinfunction "2_2") (pintype "passive"))
      (node (ref "C5") (pin "2") (pinfunction "2_2") (pintype "passive"))
      (node (ref "C6") (pin "2") (pinfunction "2_2") (pintype "passive"))
      (node (ref "C7") (pin "2") (pinfunction "2_2") (pintype "passive"))
      (node (ref "C8") (pin "2") (pinfunction "2_2") (pintype "passive"))
      (node (ref "D1") (pin "A") (pinfunction "A_A") (pintype "passive"))
      (node (ref "D2") (pin "A") (pinfunction "A_A") (pintype "passive"))
      (node (ref "IC1") (pin "2") (pinfunction "GND_2") (pintype "passive"))
      (node (ref "IC2") (pin "1") (pinfunction "OE_1") (pintype "input"))
      (node (ref "IC2") (pin "10") (pinfunction "OE_10") (pintype "input"))
      (node (ref "IC2") (pin "13") (pinfunction "OE_13") (pintype "input"))
      (node (ref "IC2") (pin "4") (pinfunction "OE_4") (pintype "input"))
      (node (ref "IC2") (pin "7") (pinfunction "GND_7") (pintype "power_in"))
      (node (ref "IC3") (pin "4") (pinfunction "GND_4") (pintype "power_in"))
      (node (ref "IC4") (pin "2") (pinfunction "GND_2") (pintype "passive"))
      (node (ref "J1") (pin "2") (pinfunction "2_2") (pintype "passive"))
      (node (ref "J1") (pin "3") (pinfunction "3_3") (pintype "passive"))
      (node (ref "J2") (pin "3") (pinfunction "3_3") (pintype "passive"))
      (node (ref "J3") (pin "1") (pinfunction "1_1") (pintype "passive"))
      (node (ref "J4") (pin "1") (pinfunction "1_1") (pintype "passive"))
      (node (ref "JP1") (pin "3") (pinfunction "3_3") (pintype "passive"))
      (node (ref "JP10") (pin "3") (pinfunction "3_3") (pintype "passive"))
      (node (ref "JP11") (pin "3") (pinfunction "3_3") (pintype "passive"))
      (node (ref "JP12") (pin "3") (pinfunction "3_3") (pintype "passive"))
      (node (ref "JP13") (pin "4") (pinfunction "4_4") (pintype "passive"))
      (node (ref "JP14") (pin "1") (pinfunction "1_1") (pintype "passive"))
      (node (ref "JP15") (pin "1") (pinfunction "1_1") (pintype "passive"))
      (node (ref "JP16") (pin "2") (pinfunction "2_2") (pintype "passive"))
      (node (ref "JP18") (pin "2") (pinfunction "2_2") (pintype "passive"))
      (node (ref "JP19") (pin "2") (pinfunction "2_2") (pintype "passive"))
      (node (ref "JP2") (pin "1") (pinfunction "1_1") (pintype "passive"))
      (node (ref "JP20") (pin "1") (pinfunction "1_1") (pintype "passive"))
      (node (ref "JP3") (pin "1") (pinfunction "1_1") (pintype "passive"))
      (node (ref "JP4") (pin "1") (pinfunction "1_1") (pintype "passive"))
      (node (ref "JP5") (pin "3") (pinfunction "3_3") (pintype "passive"))
      (node (ref "JP6") (pin "3") (pinfunction "3_3") (pintype "passive"))
      (node (ref "JP8") (pin "3") (pinfunction "3_3") (pintype "passive"))
      (node (ref "JP9") (pin "3") (pinfunction "3_3") (pintype "passive"))
      (node (ref "PAD1") (pin "1") (pinfunction "P_1") (pintype "passive"))
      (node (ref "POWER") (pin "6") (pinfunction "6_6") (pintype "passive"))
      (node (ref "POWER") (pin "7") (pinfunction "7_7") (pintype "passive"))
      (node (ref "Q2") (pin "E") (pinfunction "E_E") (pintype "passive"))
      (node (ref "R1") (pin "1") (pinfunction "1_1") (pintype "passive"))
      (node (ref "R11") (pin "1") (pinfunction "1_1") (pintype "passive"))
      (node (ref "R12") (pin "1") (pinfunction "1_1") (pintype "passive"))
      (node (ref "R7") (pin "1") (pinfunction "1_1") (pintype "passive"))
      (node (ref "S3") (pin "3") (pinfunction "P_3") (pintype "passive"))
      (node (ref "S3") (pin "4") (pinfunction "P1_4") (pintype "passive"))
      (node (ref "S4") (pin "3") (pinfunction "P_3") (pintype "passive"))
      (node (ref "S4") (pin "4") (pinfunction "P1_4") (pintype "passive"))
      (node (ref "S5") (pin "3") (pinfunction "P_3") (pintype "passive"))
      (node (ref "S5") (pin "4") (pinfunction "P1_4") (pintype "passive"))
      (node (ref "S6") (pin "3") (pinfunction "P_3") (pintype "passive"))
      (node (ref "S6") (pin "4") (pinfunction "P1_4") (pintype "passive"))
      (node (ref "S7") (pin "3") (pinfunction "P_3") (pintype "passive"))
      (node (ref "S7") (pin "4") (pinfunction "P1_4") (pintype "passive"))
      (node (ref "SV1") (pin "3") (pinfunction "3_3") (pintype "passive"))
      (node (ref "X1") (pin "3") (pinfunction "KL_3") (pintype "passive"))
      (node (ref "X10") (pin "3") (pinfunction "KL_3") (pintype "passive"))
      (node (ref "X11") (pin "2") (pinfunction "KL_2") (pintype "passive"))
      (node (ref "X12") (pin "2") (pinfunction "KL_2") (pintype "passive"))
      (node (ref "X13") (pin "3") (pinfunction "KL_3") (pintype "passive"))
      (node (ref "X14") (pin "2") (pinfunction "KL_2") (pintype "passive"))
      (node (ref "X2") (pin "3") (pinfunction "KL_3") (pintype "passive"))
      (node (ref "X3") (pin "3") (pinfunction "KL_3") (pintype "passive"))
      (node (ref "X4") (pin "3") (pinfunction "KL_3") (pintype "passive"))
      (node (ref "X5") (pin "3") (pinfunction "KL_3") (pintype "passive"))
      (node (ref "X6") (pin "3") (pinfunction "KL_3") (pintype "passive"))
      (node (ref "X7") (pin "3") (pinfunction "KL_3") (pintype "passive"))
      (node (ref "X8") (pin "3") (pinfunction "KL_3") (pintype "passive"))
      (node (ref "X9") (pin "3") (pinfunction "KL_3") (pintype "passive"))
      (node (ref "XIO") (pin "35") (pinfunction "35_35") (pintype "passive"))
      (node (ref "XIO") (pin "36") (pinfunction "36_36") (pintype "passive"))
    )
    (net (code "35") (name "LED1G") (class "Default")
      (node (ref "R21") (pin "2") (pinfunction "2_2") (pintype "passive"))
      (node (ref "XIO") (pin "6") (pinfunction "6_6") (pintype "passive"))
    )
    (net (code "36") (name "LED1R") (class "Default")
      (node (ref "R16") (pin "1") (pinfunction "1_1") (pintype "passive"))
      (node (ref "XIO") (pin "4") (pinfunction "4_4") (pintype "passive"))
    )
    (net (code "37") (name "LED2G") (class "Default")
      (node (ref "R22") (pin "2") (pinfunction "2_2") (pintype "passive"))
      (node (ref "XIO") (pin "10") (pinfunction "10_10") (pintype "passive"))
    )
    (net (code "38") (name "LED2R") (class "Default")
      (node (ref "R17") (pin "1") (pinfunction "1_1") (pintype "passive"))
      (node (ref "XIO") (pin "8") (pinfunction "8_8") (pintype "passive"))
    )
    (net (code "39") (name "LED3G") (class "Default")
      (node (ref "R23") (pin "2") (pinfunction "2_2") (pintype "passive"))
      (node (ref "XIO") (pin "14") (pinfunction "14_14") (pintype "passive"))
    )
    (net (code "40") (name "LED3R") (class "Default")
      (node (ref "R18") (pin "1") (pinfunction "1_1") (pintype "passive"))
      (node (ref "XIO") (pin "12") (pinfunction "12_12") (pintype "passive"))
    )
    (net (code "41") (name "LED4G") (class "Default")
      (node (ref "R24") (pin "2") (pinfunction "2_2") (pintype "passive"))
      (node (ref "XIO") (pin "18") (pinfunction "18_18") (pintype "passive"))
    )
    (net (code "42") (name "LED4R") (class "Default")
      (node (ref "R19") (pin "1") (pinfunction "1_1") (pintype "passive"))
      (node (ref "XIO") (pin "16") (pinfunction "16_16") (pintype "passive"))
    )
    (net (code "43") (name "LED5G") (class "Default")
      (node (ref "R25") (pin "2") (pinfunction "2_2") (pintype "passive"))
      (node (ref "XIO") (pin "26") (pinfunction "26_26") (pintype "passive"))
    )
    (net (code "44") (name "LED5R") (class "Default")
      (node (ref "R20") (pin "1") (pinfunction "1_1") (pintype "passive"))
      (node (ref "XIO") (pin "24") (pinfunction "24_24") (pintype "passive"))
    )
    (net (code "45") (name "MISO") (class "Default")
      (node (ref "R27") (pin "1") (pinfunction "1_1") (pintype "passive"))
      (node (ref "XIO") (pin "31") (pinfunction "31_31") (pintype "passive"))
    )
    (net (code "46") (name "MISO(DO)") (class "Default")
      (node (ref "JP18") (pin "3") (pinfunction "3_3") (pintype "passive"))
      (node (ref "R27") (pin "2") (pinfunction "2_2") (pintype "passive"))
    )
    (net (code "47") (name "MOSI") (class "Default")
      (node (ref "IC2") (pin "5") (pinfunction "I_5") (pintype "input"))
      (node (ref "XIO") (pin "32") (pinfunction "32_32") (pintype "passive"))
    )
    (net (code "48") (name "MOSI(DI)") (class "Default")
      (node (ref "IC2") (pin "6") (pinfunction "O_6") (pintype "tri_state"))
      (node (ref "JP18") (pin "4") (pinfunction "4_4") (pintype "passive"))
    )
    (net (code "49") (name "Net-(IC1-VO)") (class "Default")
      (node (ref "F1") (pin "2") (pinfunction "2_2") (pintype "passive"))
      (node (ref "IC1") (pin "3") (pinfunction "VO_3") (pintype "passive"))
      (node (ref "LED1") (pin "A") (pinfunction "A_A") (pintype "passive"))
    )
    (net (code "50") (name "Net-(IC2E-VCC)") (class "Default")
      (node (ref "IC2") (pin "14") (pinfunction "VCC_14") (pintype "power_in"))
      (node (ref "JP17") (pin "2") (pinfunction "2_2") (pintype "passive"))
    )
    (net (code "51") (name "Net-(IC3-VBAT)") (class "Default")
      (node (ref "IC3") (pin "3") (pinfunction "VBAT_3") (pintype "passive"))
      (node (ref "JP19") (pin "1") (pinfunction "1_1") (pintype "passive"))
    )
    (net (code "52") (name "Net-(IC3-X1)") (class "Default")
      (node (ref "IC3") (pin "1") (pinfunction "X1_1") (pintype "input"))
      (node (ref "Q1") (pin "2") (pinfunction "2_2") (pintype "passive"))
    )
    (net (code "53") (name "Net-(IC3-X2)") (class "Default")
      (node (ref "IC3") (pin "2") (pinfunction "X2_2") (pintype "output"))
      (node (ref "Q1") (pin "1") (pinfunction "1_1") (pintype "passive"))
    )
    (net (code "54") (name "Net-(IC4-VI)") (class "Default")
      (node (ref "IC4") (pin "1") (pinfunction "VI_1") (pintype "input"))
      (node (ref "J1") (pin "1") (pinfunction "1_1") (pintype "passive"))
    )
    (net (code "55") (name "Net-(JP16-Pad1)") (class "Default")
      (node (ref "JP16") (pin "1") (pinfunction "1_1") (pintype "passive"))
      (node (ref "R26") (pin "2") (pinfunction "2_2") (pintype "passive"))
    )
    (net (code "56") (name "Net-(LD1-CG)") (class "Default")
      (node (ref "LD1") (pin "CX") (pinfunction "CG_CX") (pintype "passive"))
      (node (ref "R21") (pin "1") (pinfunction "1_1") (pintype "passive"))
    )
    (net (code "57") (name "Net-(LD1-PadCR)") (class "Default")
      (node (ref "LD1") (pin "CR") (pinfunction "CR_CR") (pintype "passive"))
      (node (ref "R16") (pin "2") (pinfunction "2_2") (pintype "passive"))
    )
    (net (code "58") (name "Net-(LD2-CG)") (class "Default")
      (node (ref "LD2") (pin "CX") (pinfunction "CG_CX") (pintype "passive"))
      (node (ref "R22") (pin "1") (pinfunction "1_1") (pintype "passive"))
    )
    (net (code "59") (name "Net-(LD2-PadCR)") (class "Default")
      (node (ref "LD2") (pin "CR") (pinfunction "CR_CR") (pintype "passive"))
      (node (ref "R17") (pin "2") (pinfunction "2_2") (pintype "passive"))
    )
    (net (code "60") (name "Net-(LD3-CG)") (class "Default")
      (node (ref "LD3") (pin "CX") (pinfunction "CG_CX") (pintype "passive"))
      (node (ref "R23") (pin "1") (pinfunction "1_1") (pintype "passive"))
    )
    (net (code "61") (name "Net-(LD3-PadCR)") (class "Default")
      (node (ref "LD3") (pin "CR") (pinfunction "CR_CR") (pintype "passive"))
      (node (ref "R18") (pin "2") (pinfunction "2_2") (pintype "passive"))
    )
    (net (code "62") (name "Net-(LD4-CG)") (class "Default")
      (node (ref "LD4") (pin "CX") (pinfunction "CG_CX") (pintype "passive"))
      (node (ref "R24") (pin "1") (pinfunction "1_1") (pintype "passive"))
    )
    (net (code "63") (name "Net-(LD4-PadCR)") (class "Default")
      (node (ref "LD4") (pin "CR") (pinfunction "CR_CR") (pintype "passive"))
      (node (ref "R19") (pin "2") (pinfunction "2_2") (pintype "passive"))
    )
    (net (code "64") (name "Net-(LD5-CG)") (class "Default")
      (node (ref "LD5") (pin "CX") (pinfunction "CG_CX") (pintype "passive"))
      (node (ref "R25") (pin "1") (pinfunction "1_1") (pintype "passive"))
    )
    (net (code "65") (name "Net-(LD5-PadCR)") (class "Default")
      (node (ref "LD5") (pin "CR") (pinfunction "CR_CR") (pintype "passive"))
      (node (ref "R20") (pin "2") (pinfunction "2_2") (pintype "passive"))
    )
    (net (code "66") (name "Net-(LED1-C)") (class "Default")
      (node (ref "LED1") (pin "K") (pinfunction "C_K") (pintype "passive"))
      (node (ref "R1") (pin "2") (pinfunction "2_2") (pintype "passive"))
    )
    (net (code "67") (name "Net-(Q2-PadB)") (class "Default")
      (node (ref "Q2") (pin "B") (pinfunction "B_B") (pintype "passive"))
      (node (ref "R30") (pin "2") (pinfunction "2_2") (pintype "passive"))
    )
    (net (code "68") (name "Net-(Q2-PadC)") (class "Default")
      (node (ref "Q2") (pin "C") (pinfunction "C_C") (pintype "passive"))
      (node (ref "R31") (pin "1") (pinfunction "1_1") (pintype "passive"))
      (node (ref "R32") (pin "2") (pinfunction "2_2") (pintype "passive"))
    )
    (net (code "69") (name "Net-(R3-Pad2)") (class "Default")
      (node (ref "R3") (pin "2") (pinfunction "2_2") (pintype "passive"))
      (node (ref "R4") (pin "2") (pinfunction "2_2") (pintype "passive"))
    )
    (net (code "70") (name "Net-(R4-Pad1)") (class "Default")
      (node (ref "R4") (pin "1") (pinfunction "1_1") (pintype "passive"))
      (node (ref "R5") (pin "1") (pinfunction "1_1") (pintype "passive"))
    )
    (net (code "71") (name "Net-(R5-Pad2)") (class "Default")
      (node (ref "R5") (pin "2") (pinfunction "2_2") (pintype "passive"))
      (node (ref "R6") (pin "2") (pinfunction "2_2") (pintype "passive"))
    )
    (net (code "72") (name "Net-(R10-Pad2)") (class "Default")
      (node (ref "R10") (pin "2") (pinfunction "2_2") (pintype "passive"))
      (node (ref "R9") (pin "1") (pinfunction "1_1") (pintype "passive"))
    )
    (net (code "73") (name "Net-(R13-Pad1)") (class "Default")
      (node (ref "R13") (pin "1") (pinfunction "1_1") (pintype "passive"))
      (node (ref "R14") (pin "2") (pinfunction "2_2") (pintype "passive"))
    )
    (net (code "74") (name "Net-(R14-Pad1)") (class "Default")
      (node (ref "R14") (pin "1") (pinfunction "1_1") (pintype "passive"))
      (node (ref "R15") (pin "2") (pinfunction "2_2") (pintype "passive"))
    )
    (net (code "75") (name "Net-(S2-O)") (class "Default")
      (node (ref "R3") (pin "1") (pinfunction "1_1") (pintype "passive"))
      (node (ref "R8") (pin "2") (pinfunction "2_2") (pintype "passive"))
      (node (ref "S2") (pin "3") (pinfunction "O_3") (pintype "passive"))
    )
    (net (code "76") (name "Net-(S2-P)") (class "Default")
      (node (ref "S2") (pin "2") (pinfunction "P_2") (pintype "passive"))
      (node (ref "X11") (pin "1") (pinfunction "KL_1") (pintype "passive"))
    )
    (net (code "77") (name "Net-(S2-S)") (class "Default")
      (node (ref "R9") (pin "2") (pinfunction "2_2") (pintype "passive"))
      (node (ref "S2") (pin "1") (pinfunction "S_1") (pintype "passive"))
    )
    (net (code "78") (name "Net-(X12A-KL)") (class "Default")
      (node (ref "R13") (pin "2") (pinfunction "2_2") (pintype "passive"))
      (node (ref "X12") (pin "1") (pinfunction "KL_1") (pintype "passive"))
    )
    (net (code "79") (name "Net-(X13A-KL)") (class "Default")
      (node (ref "R31") (pin "2") (pinfunction "2_2") (pintype "passive"))
      (node (ref "X13") (pin "1") (pinfunction "KL_1") (pintype "passive"))
    )
    (net (code "80") (name "Net-(X13B-KL)") (class "Default")
      (node (ref "C8") (pin "1") (pinfunction "1_1") (pintype "passive"))
      (node (ref "R32") (pin "1") (pinfunction "1_1") (pintype "passive"))
      (node (ref "X13") (pin "2") (pinfunction "KL_2") (pintype "passive"))
    )
    (net (code "81") (name "PIEZZO") (class "Default")
      (node (ref "ADCH") (pin "4") (pinfunction "4_4") (pintype "passive"))
      (node (ref "JP12") (pin "2") (pinfunction "2_2") (pintype "passive"))
    )
    (net (code "82") (name "PRESURE1") (class "Default")
      (node (ref "ADCL") (pin "2") (pinfunction "2_2") (pintype "passive"))
      (node (ref "X4") (pin "2") (pinfunction "KL_2") (pintype "passive"))
    )
    (net (code "83") (name "PRESURE2") (class "Default")
      (node (ref "ADCL") (pin "1") (pinfunction "1_1") (pintype "passive"))
      (node (ref "X6") (pin "2") (pinfunction "KL_2") (pintype "passive"))
    )
    (net (code "84") (name "RELEAY1") (class "Default")
      (node (ref "JP4") (pin "3") (pinfunction "3_3") (pintype "passive"))
      (node (ref "XIO") (pin "25") (pinfunction "25_25") (pintype "passive"))
    )
    (net (code "85") (name "RELEAY2") (class "Default")
      (node (ref "JP4") (pin "4") (pinfunction "4_4") (pintype "passive"))
      (node (ref "XIO") (pin "27") (pinfunction "27_27") (pintype "passive"))
    )
    (net (code "86") (name "RX1") (class "Default")
      (node (ref "COMMUNICATION") (pin "3") (pinfunction "3_3") (pintype "passive"))
      (node (ref "JP1") (pin "2") (pinfunction "2_2") (pintype "passive"))
    )
    (net (code "87") (name "RX2") (class "Default")
      (node (ref "COMMUNICATION") (pin "5") (pinfunction "5_5") (pintype "passive"))
      (node (ref "JP7") (pin "4") (pinfunction "4_4") (pintype "passive"))
    )
    (net (code "88") (name "RX3") (class "Default")
      (node (ref "COMMUNICATION") (pin "7") (pinfunction "7_7") (pintype "passive"))
      (node (ref "JP7") (pin "2") (pinfunction "2_2") (pintype "passive"))
    )
    (net (code "89") (name "SCK") (class "Default")
      (node (ref "IC2") (pin "9") (pinfunction "I_9") (pintype "input"))
      (node (ref "XIO") (pin "33") (pinfunction "33_33") (pintype "passive"))
    )
    (net (code "90") (name "SCL") (class "Default")
      (node (ref "IC3") (pin "6") (pinfunction "SCL_6") (pintype "input"))
      (node (ref "JP13") (pin "1") (pinfunction "1_1") (pintype "passive"))
      (node (ref "R29") (pin "2") (pinfunction "2_2") (pintype "passive"))
    )
    (net (code "91") (name "SCL-EXT") (class "Default")
      (node (ref "COMMUNICATION") (pin "1") (pinfunction "1_1") (pintype "passive"))
      (node (ref "JP2") (pin "3") (pinfunction "3_3") (pintype "passive"))
    )
    (net (code "92") (name "SCLK") (class "Default")
      (node (ref "IC2") (pin "8") (pinfunction "O_8") (pintype "tri_state"))
      (node (ref "JP18") (pin "5") (pinfunction "5_5") (pintype "passive"))
    )
    (net (code "93") (name "SDA") (class "Default")
      (node (ref "IC3") (pin "5") (pinfunction "SDA_5") (pintype "bidirectional"))
      (node (ref "JP13") (pin "2") (pinfunction "2_2") (pintype "passive"))
      (node (ref "R28") (pin "2") (pinfunction "2_2") (pintype "passive"))
    )
    (net (code "94") (name "SDA-EXT") (class "Default")
      (node (ref "COMMUNICATION") (pin "2") (pinfunction "2_2") (pintype "passive"))
      (node (ref "JP2") (pin "4") (pinfunction "4_4") (pintype "passive"))
    )
    (net (code "95") (name "SS") (class "Default")
      (node (ref "IC2") (pin "12") (pinfunction "I_12") (pintype "input"))
      (node (ref "JP13") (pin "10") (pinfunction "10_10") (pintype "passive"))
    )
    (net (code "96") (name "TACHO1") (class "Default")
      (node (ref "JP3") (pin "3") (pinfunction "3_3") (pintype "passive"))
      (node (ref "PWML") (pin "4") (pinfunction "4_4") (pintype "passive"))
    )
    (net (code "97") (name "TACHO2") (class "Default")
      (node (ref "JP3") (pin "4") (pinfunction "4_4") (pintype "passive"))
      (node (ref "PWML") (pin "3") (pinfunction "3_3") (pintype "passive"))
    )
    (net (code "98") (name "TX1") (class "Default")
      (node (ref "COMMUNICATION") (pin "4") (pinfunction "4_4") (pintype "passive"))
      (node (ref "JP1") (pin "1") (pinfunction "1_1") (pintype "passive"))
    )
    (net (code "99") (name "TX2") (class "Default")
      (node (ref "COMMUNICATION") (pin "6") (pinfunction "6_6") (pintype "passive"))
      (node (ref "JP7") (pin "3") (pinfunction "3_3") (pintype "passive"))
    )
    (net (code "100") (name "TX3") (class "Default")
      (node (ref "COMMUNICATION") (pin "8") (pinfunction "8_8") (pintype "passive"))
      (node (ref "JP7") (pin "1") (pinfunction "1_1") (pintype "passive"))
    )
    (net (code "101") (name "WATER") (class "Default")
      (node (ref "ADCH") (pin "2") (pinfunction "2_2") (pintype "passive"))
      (node (ref "JP6") (pin "2") (pinfunction "2_2") (pintype "passive"))
    )
    (net (code "102") (name "WS2812") (class "Default")
      (node (ref "ADCH") (pin "1") (pinfunction "1_1") (pintype "passive"))
      (node (ref "J2") (pin "2") (pinfunction "2_2") (pintype "passive"))
    )
    (net (code "103") (name "X") (class "Default")
      (node (ref "ADCL") (pin "3") (pinfunction "3_3") (pintype "passive"))
      (node (ref "SV1") (pin "9") (pinfunction "9_9") (pintype "passive"))
    )
    (net (code "104") (name "Y") (class "Default")
      (node (ref "ADCL") (pin "4") (pinfunction "4_4") (pintype "passive"))
      (node (ref "SV1") (pin "7") (pinfunction "7_7") (pintype "passive"))
    )
    (net (code "105") (name "Z") (class "Default")
      (node (ref "ADCL") (pin "5") (pinfunction "5_5") (pintype "passive"))
      (node (ref "SV1") (pin "5") (pinfunction "5_5") (pintype "passive"))
    )
    (net (code "106") (name "unconnected-(IC2A-I-Pad2)") (class "Default")
      (node (ref "IC2") (pin "2") (pinfunction "I_2") (pintype "input"))
    )
    (net (code "107") (name "unconnected-(IC2A-O-Pad3)") (class "Default")
      (node (ref "IC2") (pin "3") (pinfunction "O_3") (pintype "tri_state"))
    )
    (net (code "108") (name "unconnected-(IC3-SQW-Pad7)") (class "Default")
      (node (ref "IC3") (pin "7") (pinfunction "SQW_7") (pintype "open_collector"))
    )
    (net (code "109") (name "unconnected-(JP13-Pad3)") (class "Default")
      (node (ref "JP13") (pin "3") (pinfunction "3_3") (pintype "passive"))
    )
    (net (code "110") (name "unconnected-(POWER-Pad1)") (class "Default")
      (node (ref "POWER") (pin "1") (pinfunction "1_1") (pintype "passive"))
    )
    (net (code "111") (name "unconnected-(POWER-Pad2)") (class "Default")
      (node (ref "POWER") (pin "2") (pinfunction "2_2") (pintype "passive"))
    )
    (net (code "112") (name "unconnected-(POWER-Pad3)") (class "Default")
      (node (ref "POWER") (pin "3") (pinfunction "3_3") (pintype "passive"))
    )
    (net (code "113") (name "unconnected-(POWER-Pad8)") (class "Default")
      (node (ref "POWER") (pin "8") (pinfunction "8_8") (pintype "passive"))
    )
    (net (code "114") (name "unconnected-(PWML-Pad1)") (class "Default")
      (node (ref "PWML") (pin "1") (pinfunction "1_1") (pintype "passive"))
    )
    (net (code "115") (name "unconnected-(PWML-Pad2)") (class "Default")
      (node (ref "PWML") (pin "2") (pinfunction "2_2") (pintype "passive"))
    )
    (net (code "116") (name "unconnected-(XIO-Pad13)") (class "Default")
      (node (ref "XIO") (pin "13") (pinfunction "13_13") (pintype "passive"))
    )
    (net (code "117") (name "unconnected-(XIO-Pad15)") (class "Default")
      (node (ref "XIO") (pin "15") (pinfunction "15_15") (pintype "passive"))
    )
    (net (code "118") (name "unconnected-(XIO-Pad17)") (class "Default")
      (node (ref "XIO") (pin "17") (pinfunction "17_17") (pintype "passive"))
    )
    (net (code "119") (name "unconnected-(XIO-Pad23)") (class "Default")
      (node (ref "XIO") (pin "23") (pinfunction "23_23") (pintype "passive"))
    )
    (net (code "120") (name "unconnected-(XIO-Pad28)") (class "Default")
      (node (ref "XIO") (pin "28") (pinfunction "28_28") (pintype "passive"))
    )
    (net (code "121") (name "unconnected-(XIO-Pad29)") (class "Default")
      (node (ref "XIO") (pin "29") (pinfunction "29_29") (pintype "passive"))
    )
    (net (code "122") (name "unconnected-(XIO-Pad30)") (class "Default")
      (node (ref "XIO") (pin "30") (pinfunction "30_30") (pintype "passive"))
    )
    (net (code "123") (name "unconnected-(XIO-Pad34)") (class "Default")
      (node (ref "XIO") (pin "34") (pinfunction "34_34") (pintype "passive"))
    )
  )
)
